# Insole_ver1_chi.net
KiCad netlist of a schematic drawn in Altium Designer
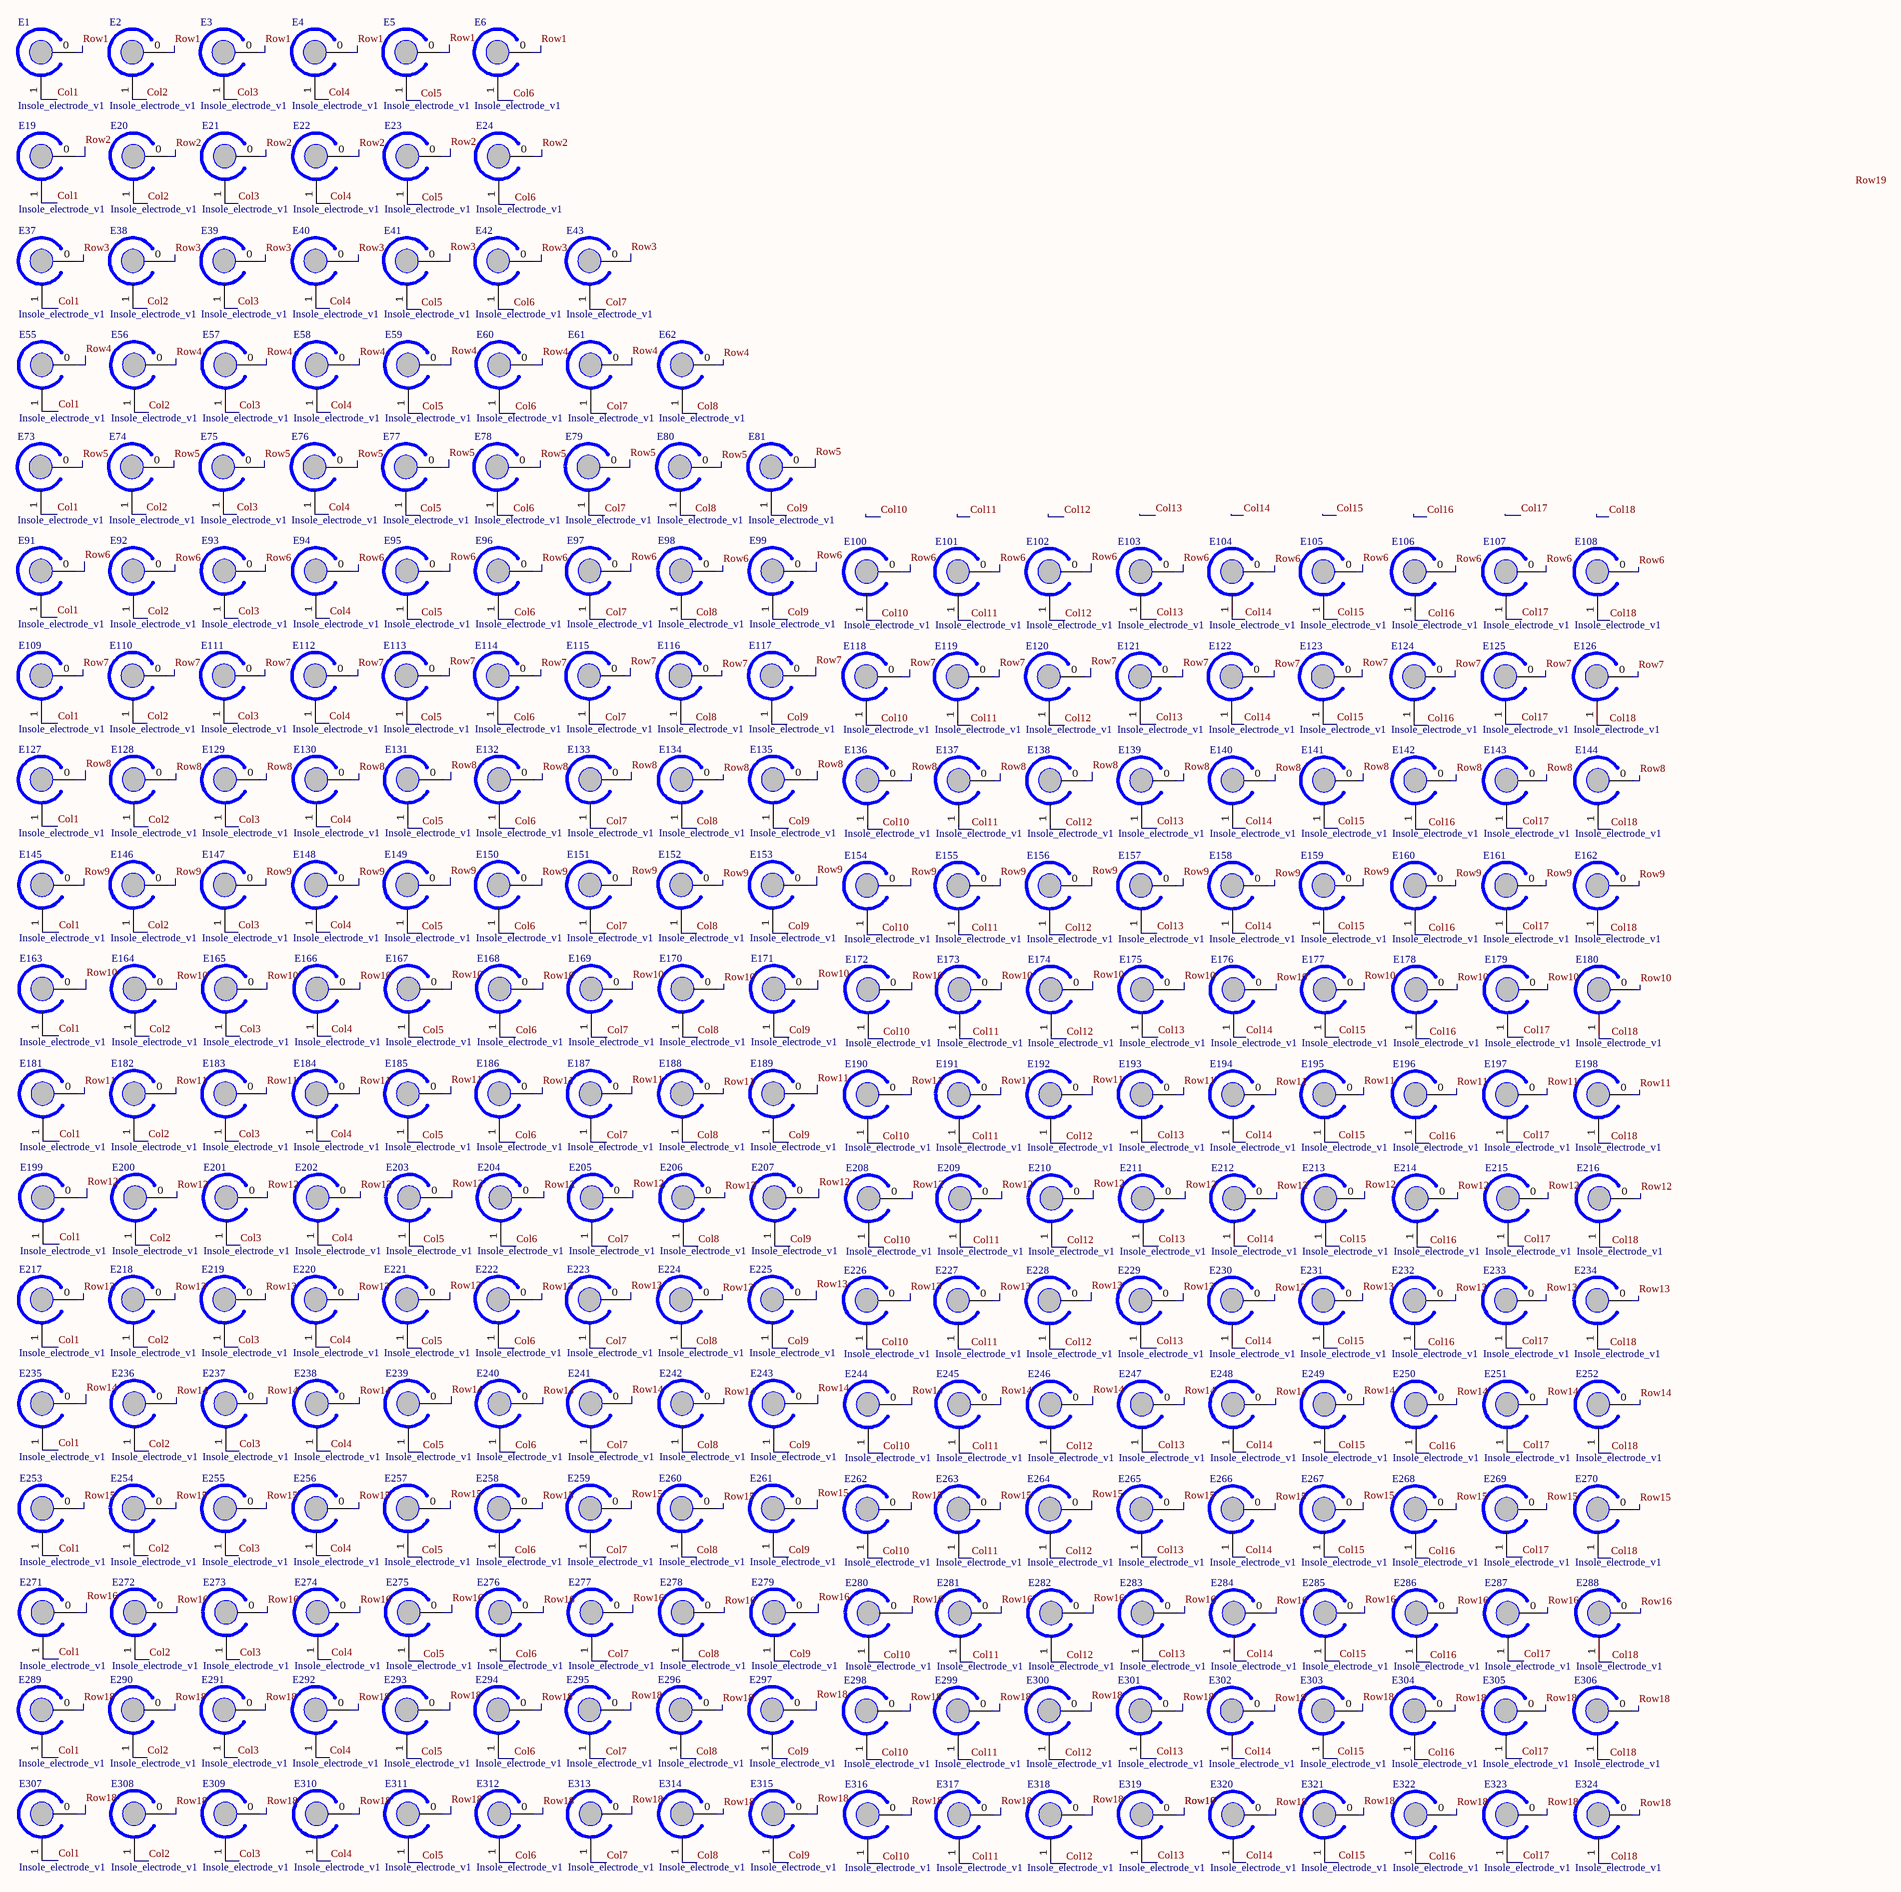
[diagram p0: Insole_ver1_chi.SchDoc]

(export (version "E")
  (design (tool "Eeschema 10.0.6"))
  (components
    (comp (ref "E1")
      (value "Insole_electrode_v1")
      (footprint "insole_electrode_v1")
      (libsource (lib "UCL") (part "Insole_electrode_v1"))
    )
    (comp (ref "E2")
      (value "Insole_electrode_v1")
      (footprint "insole_electrode_v1")
      (libsource (lib "UCL") (part "Insole_electrode_v1"))
    )
    (comp (ref "E3")
      (value "Insole_electrode_v1")
      (footprint "insole_electrode_v1")
      (libsource (lib "UCL") (part "Insole_electrode_v1"))
    )
    (comp (ref "E4")
      (value "Insole_electrode_v1")
      (footprint "insole_electrode_v1")
      (libsource (lib "UCL") (part "Insole_electrode_v1"))
    )
    (comp (ref "E5")
      (value "Insole_electrode_v1")
      (footprint "insole_electrode_v1")
      (libsource (lib "UCL") (part "Insole_electrode_v1"))
    )
    (comp (ref "E6")
      (value "Insole_electrode_v1")
      (footprint "insole_electrode_v1")
      (libsource (lib "UCL") (part "Insole_electrode_v1"))
    )
    (comp (ref "E19")
      (value "Insole_electrode_v1")
      (footprint "insole_electrode_v1")
      (libsource (lib "UCL") (part "Insole_electrode_v1"))
    )
    (comp (ref "E20")
      (value "Insole_electrode_v1")
      (footprint "insole_electrode_v1")
      (libsource (lib "UCL") (part "Insole_electrode_v1"))
    )
    (comp (ref "E21")
      (value "Insole_electrode_v1")
      (footprint "insole_electrode_v1")
      (libsource (lib "UCL") (part "Insole_electrode_v1"))
    )
    (comp (ref "E22")
      (value "Insole_electrode_v1")
      (footprint "insole_electrode_v1")
      (libsource (lib "UCL") (part "Insole_electrode_v1"))
    )
    (comp (ref "E23")
      (value "Insole_electrode_v1")
      (footprint "insole_electrode_v1")
      (libsource (lib "UCL") (part "Insole_electrode_v1"))
    )
    (comp (ref "E24")
      (value "Insole_electrode_v1")
      (footprint "insole_electrode_v1")
      (libsource (lib "UCL") (part "Insole_electrode_v1"))
    )
    (comp (ref "E37")
      (value "Insole_electrode_v1")
      (footprint "insole_electrode_v1")
      (libsource (lib "UCL") (part "Insole_electrode_v1"))
    )
    (comp (ref "E38")
      (value "Insole_electrode_v1")
      (footprint "insole_electrode_v1")
      (libsource (lib "UCL") (part "Insole_electrode_v1"))
    )
    (comp (ref "E39")
      (value "Insole_electrode_v1")
      (footprint "insole_electrode_v1")
      (libsource (lib "UCL") (part "Insole_electrode_v1"))
    )
    (comp (ref "E40")
      (value "Insole_electrode_v1")
      (footprint "insole_electrode_v1")
      (libsource (lib "UCL") (part "Insole_electrode_v1"))
    )
    (comp (ref "E41")
      (value "Insole_electrode_v1")
      (footprint "insole_electrode_v1")
      (libsource (lib "UCL") (part "Insole_electrode_v1"))
    )
    (comp (ref "E42")
      (value "Insole_electrode_v1")
      (footprint "insole_electrode_v1")
      (libsource (lib "UCL") (part "Insole_electrode_v1"))
    )
    (comp (ref "E43")
      (value "Insole_electrode_v1")
      (footprint "insole_electrode_v1")
      (libsource (lib "UCL") (part "Insole_electrode_v1"))
    )
    (comp (ref "E55")
      (value "Insole_electrode_v1")
      (footprint "insole_electrode_v1")
      (libsource (lib "UCL") (part "Insole_electrode_v1"))
    )
    (comp (ref "E56")
      (value "Insole_electrode_v1")
      (footprint "insole_electrode_v1")
      (libsource (lib "UCL") (part "Insole_electrode_v1"))
    )
    (comp (ref "E57")
      (value "Insole_electrode_v1")
      (footprint "insole_electrode_v1")
      (libsource (lib "UCL") (part "Insole_electrode_v1"))
    )
    (comp (ref "E58")
      (value "Insole_electrode_v1")
      (footprint "insole_electrode_v1")
      (libsource (lib "UCL") (part "Insole_electrode_v1"))
    )
    (comp (ref "E59")
      (value "Insole_electrode_v1")
      (footprint "insole_electrode_v1")
      (libsource (lib "UCL") (part "Insole_electrode_v1"))
    )
    (comp (ref "E60")
      (value "Insole_electrode_v1")
      (footprint "insole_electrode_v1")
      (libsource (lib "UCL") (part "Insole_electrode_v1"))
    )
    (comp (ref "E61")
      (value "Insole_electrode_v1")
      (footprint "insole_electrode_v1")
      (libsource (lib "UCL") (part "Insole_electrode_v1"))
    )
    (comp (ref "E62")
      (value "Insole_electrode_v1")
      (footprint "insole_electrode_v1")
      (libsource (lib "UCL") (part "Insole_electrode_v1"))
    )
    (comp (ref "E73")
      (value "Insole_electrode_v1")
      (footprint "insole_electrode_v1")
      (libsource (lib "UCL") (part "Insole_electrode_v1"))
    )
    (comp (ref "E74")
      (value "Insole_electrode_v1")
      (footprint "insole_electrode_v1")
      (libsource (lib "UCL") (part "Insole_electrode_v1"))
    )
    (comp (ref "E75")
      (value "Insole_electrode_v1")
      (footprint "insole_electrode_v1")
      (libsource (lib "UCL") (part "Insole_electrode_v1"))
    )
    (comp (ref "E76")
      (value "Insole_electrode_v1")
      (footprint "insole_electrode_v1")
      (libsource (lib "UCL") (part "Insole_electrode_v1"))
    )
    (comp (ref "E77")
      (value "Insole_electrode_v1")
      (footprint "insole_electrode_v1")
      (libsource (lib "UCL") (part "Insole_electrode_v1"))
    )
    (comp (ref "E78")
      (value "Insole_electrode_v1")
      (footprint "insole_electrode_v1")
      (libsource (lib "UCL") (part "Insole_electrode_v1"))
    )
    (comp (ref "E79")
      (value "Insole_electrode_v1")
      (footprint "insole_electrode_v1")
      (libsource (lib "UCL") (part "Insole_electrode_v1"))
    )
    (comp (ref "E80")
      (value "Insole_electrode_v1")
      (footprint "insole_electrode_v1")
      (libsource (lib "UCL") (part "Insole_electrode_v1"))
    )
    (comp (ref "E81")
      (value "Insole_electrode_v1")
      (footprint "insole_electrode_v1")
      (libsource (lib "UCL") (part "Insole_electrode_v1"))
    )
    (comp (ref "E91")
      (value "Insole_electrode_v1")
      (footprint "insole_electrode_v1")
      (libsource (lib "UCL") (part "Insole_electrode_v1"))
    )
    (comp (ref "E92")
      (value "Insole_electrode_v1")
      (footprint "insole_electrode_v1")
      (libsource (lib "UCL") (part "Insole_electrode_v1"))
    )
    (comp (ref "E93")
      (value "Insole_electrode_v1")
      (footprint "insole_electrode_v1")
      (libsource (lib "UCL") (part "Insole_electrode_v1"))
    )
    (comp (ref "E94")
      (value "Insole_electrode_v1")
      (footprint "insole_electrode_v1")
      (libsource (lib "UCL") (part "Insole_electrode_v1"))
    )
    (comp (ref "E95")
      (value "Insole_electrode_v1")
      (footprint "insole_electrode_v1")
      (libsource (lib "UCL") (part "Insole_electrode_v1"))
    )
    (comp (ref "E96")
      (value "Insole_electrode_v1")
      (footprint "insole_electrode_v1")
      (libsource (lib "UCL") (part "Insole_electrode_v1"))
    )
    (comp (ref "E97")
      (value "Insole_electrode_v1")
      (footprint "insole_electrode_v1")
      (libsource (lib "UCL") (part "Insole_electrode_v1"))
    )
    (comp (ref "E98")
      (value "Insole_electrode_v1")
      (footprint "insole_electrode_v1")
      (libsource (lib "UCL") (part "Insole_electrode_v1"))
    )
    (comp (ref "E99")
      (value "Insole_electrode_v1")
      (footprint "insole_electrode_v1")
      (libsource (lib "UCL") (part "Insole_electrode_v1"))
    )
    (comp (ref "E100")
      (value "Insole_electrode_v1")
      (footprint "insole_electrode_v1")
      (libsource (lib "UCL") (part "Insole_electrode_v1"))
    )
    (comp (ref "E101")
      (value "Insole_electrode_v1")
      (footprint "insole_electrode_v1")
      (libsource (lib "UCL") (part "Insole_electrode_v1"))
    )
    (comp (ref "E102")
      (value "Insole_electrode_v1")
      (footprint "insole_electrode_v1")
      (libsource (lib "UCL") (part "Insole_electrode_v1"))
    )
    (comp (ref "E103")
      (value "Insole_electrode_v1")
      (footprint "insole_electrode_v1")
      (libsource (lib "UCL") (part "Insole_electrode_v1"))
    )
    (comp (ref "E104")
      (value "Insole_electrode_v1")
      (footprint "insole_electrode_v1")
      (libsource (lib "UCL") (part "Insole_electrode_v1"))
    )
    (comp (ref "E105")
      (value "Insole_electrode_v1")
      (footprint "insole_electrode_v1")
      (libsource (lib "UCL") (part "Insole_electrode_v1"))
    )
    (comp (ref "E106")
      (value "Insole_electrode_v1")
      (footprint "insole_electrode_v1")
      (libsource (lib "UCL") (part "Insole_electrode_v1"))
    )
    (comp (ref "E107")
      (value "Insole_electrode_v1")
      (footprint "insole_electrode_v1")
      (libsource (lib "UCL") (part "Insole_electrode_v1"))
    )
    (comp (ref "E108")
      (value "Insole_electrode_v1")
      (footprint "insole_electrode_v1")
      (libsource (lib "UCL") (part "Insole_electrode_v1"))
    )
    (comp (ref "E109")
      (value "Insole_electrode_v1")
      (footprint "insole_electrode_v1")
      (libsource (lib "UCL") (part "Insole_electrode_v1"))
    )
    (comp (ref "E110")
      (value "Insole_electrode_v1")
      (footprint "insole_electrode_v1")
      (libsource (lib "UCL") (part "Insole_electrode_v1"))
    )
    (comp (ref "E111")
      (value "Insole_electrode_v1")
      (footprint "insole_electrode_v1")
      (libsource (lib "UCL") (part "Insole_electrode_v1"))
    )
    (comp (ref "E112")
      (value "Insole_electrode_v1")
      (footprint "insole_electrode_v1")
      (libsource (lib "UCL") (part "Insole_electrode_v1"))
    )
    (comp (ref "E113")
      (value "Insole_electrode_v1")
      (footprint "insole_electrode_v1")
      (libsource (lib "UCL") (part "Insole_electrode_v1"))
    )
    (comp (ref "E114")
      (value "Insole_electrode_v1")
      (footprint "insole_electrode_v1")
      (libsource (lib "UCL") (part "Insole_electrode_v1"))
    )
    (comp (ref "E115")
      (value "Insole_electrode_v1")
      (footprint "insole_electrode_v1")
      (libsource (lib "UCL") (part "Insole_electrode_v1"))
    )
    (comp (ref "E116")
      (value "Insole_electrode_v1")
      (footprint "insole_electrode_v1")
      (libsource (lib "UCL") (part "Insole_electrode_v1"))
    )
    (comp (ref "E117")
      (value "Insole_electrode_v1")
      (footprint "insole_electrode_v1")
      (libsource (lib "UCL") (part "Insole_electrode_v1"))
    )
    (comp (ref "E118")
      (value "Insole_electrode_v1")
      (footprint "insole_electrode_v1")
      (libsource (lib "UCL") (part "Insole_electrode_v1"))
    )
    (comp (ref "E119")
      (value "Insole_electrode_v1")
      (footprint "insole_electrode_v1")
      (libsource (lib "UCL") (part "Insole_electrode_v1"))
    )
    (comp (ref "E120")
      (value "Insole_electrode_v1")
      (footprint "insole_electrode_v1")
      (libsource (lib "UCL") (part "Insole_electrode_v1"))
    )
    (comp (ref "E121")
      (value "Insole_electrode_v1")
      (footprint "insole_electrode_v1")
      (libsource (lib "UCL") (part "Insole_electrode_v1"))
    )
    (comp (ref "E122")
      (value "Insole_electrode_v1")
      (footprint "insole_electrode_v1")
      (libsource (lib "UCL") (part "Insole_electrode_v1"))
    )
    (comp (ref "E123")
      (value "Insole_electrode_v1")
      (footprint "insole_electrode_v1")
      (libsource (lib "UCL") (part "Insole_electrode_v1"))
    )
    (comp (ref "E124")
      (value "Insole_electrode_v1")
      (footprint "insole_electrode_v1")
      (libsource (lib "UCL") (part "Insole_electrode_v1"))
    )
    (comp (ref "E125")
      (value "Insole_electrode_v1")
      (footprint "insole_electrode_v1")
      (libsource (lib "UCL") (part "Insole_electrode_v1"))
    )
    (comp (ref "E126")
      (value "Insole_electrode_v1")
      (footprint "insole_electrode_v1")
      (libsource (lib "UCL") (part "Insole_electrode_v1"))
    )
    (comp (ref "E127")
      (value "Insole_electrode_v1")
      (footprint "insole_electrode_v1")
      (libsource (lib "UCL") (part "Insole_electrode_v1"))
    )
    (comp (ref "E128")
      (value "Insole_electrode_v1")
      (footprint "insole_electrode_v1")
      (libsource (lib "UCL") (part "Insole_electrode_v1"))
    )
    (comp (ref "E129")
      (value "Insole_electrode_v1")
      (footprint "insole_electrode_v1")
      (libsource (lib "UCL") (part "Insole_electrode_v1"))
    )
    (comp (ref "E130")
      (value "Insole_electrode_v1")
      (footprint "insole_electrode_v1")
      (libsource (lib "UCL") (part "Insole_electrode_v1"))
    )
    (comp (ref "E131")
      (value "Insole_electrode_v1")
      (footprint "insole_electrode_v1")
      (libsource (lib "UCL") (part "Insole_electrode_v1"))
    )
    (comp (ref "E132")
      (value "Insole_electrode_v1")
      (footprint "insole_electrode_v1")
      (libsource (lib "UCL") (part "Insole_electrode_v1"))
    )
    (comp (ref "E133")
      (value "Insole_electrode_v1")
      (footprint "insole_electrode_v1")
      (libsource (lib "UCL") (part "Insole_electrode_v1"))
    )
    (comp (ref "E134")
      (value "Insole_electrode_v1")
      (footprint "insole_electrode_v1")
      (libsource (lib "UCL") (part "Insole_electrode_v1"))
    )
    (comp (ref "E135")
      (value "Insole_electrode_v1")
      (footprint "insole_electrode_v1")
      (libsource (lib "UCL") (part "Insole_electrode_v1"))
    )
    (comp (ref "E136")
      (value "Insole_electrode_v1")
      (footprint "insole_electrode_v1")
      (libsource (lib "UCL") (part "Insole_electrode_v1"))
    )
    (comp (ref "E137")
      (value "Insole_electrode_v1")
      (footprint "insole_electrode_v1")
      (libsource (lib "UCL") (part "Insole_electrode_v1"))
    )
    (comp (ref "E138")
      (value "Insole_electrode_v1")
      (footprint "insole_electrode_v1")
      (libsource (lib "UCL") (part "Insole_electrode_v1"))
    )
    (comp (ref "E139")
      (value "Insole_electrode_v1")
      (footprint "insole_electrode_v1")
      (libsource (lib "UCL") (part "Insole_electrode_v1"))
    )
    (comp (ref "E140")
      (value "Insole_electrode_v1")
      (footprint "insole_electrode_v1")
      (libsource (lib "UCL") (part "Insole_electrode_v1"))
    )
    (comp (ref "E141")
      (value "Insole_electrode_v1")
      (footprint "insole_electrode_v1")
      (libsource (lib "UCL") (part "Insole_electrode_v1"))
    )
    (comp (ref "E142")
      (value "Insole_electrode_v1")
      (footprint "insole_electrode_v1")
      (libsource (lib "UCL") (part "Insole_electrode_v1"))
    )
    (comp (ref "E143")
      (value "Insole_electrode_v1")
      (footprint "insole_electrode_v1")
      (libsource (lib "UCL") (part "Insole_electrode_v1"))
    )
    (comp (ref "E144")
      (value "Insole_electrode_v1")
      (footprint "insole_electrode_v1")
      (libsource (lib "UCL") (part "Insole_electrode_v1"))
    )
    (comp (ref "E145")
      (value "Insole_electrode_v1")
      (footprint "insole_electrode_v1")
      (libsource (lib "UCL") (part "Insole_electrode_v1"))
    )
    (comp (ref "E146")
      (value "Insole_electrode_v1")
      (footprint "insole_electrode_v1")
      (libsource (lib "UCL") (part "Insole_electrode_v1"))
    )
    (comp (ref "E147")
      (value "Insole_electrode_v1")
      (footprint "insole_electrode_v1")
      (libsource (lib "UCL") (part "Insole_electrode_v1"))
    )
    (comp (ref "E148")
      (value "Insole_electrode_v1")
      (footprint "insole_electrode_v1")
      (libsource (lib "UCL") (part "Insole_electrode_v1"))
    )
    (comp (ref "E149")
      (value "Insole_electrode_v1")
      (footprint "insole_electrode_v1")
      (libsource (lib "UCL") (part "Insole_electrode_v1"))
    )
    (comp (ref "E150")
      (value "Insole_electrode_v1")
      (footprint "insole_electrode_v1")
      (libsource (lib "UCL") (part "Insole_electrode_v1"))
    )
    (comp (ref "E151")
      (value "Insole_electrode_v1")
      (footprint "insole_electrode_v1")
      (libsource (lib "UCL") (part "Insole_electrode_v1"))
    )
    (comp (ref "E152")
      (value "Insole_electrode_v1")
      (footprint "insole_electrode_v1")
      (libsource (lib "UCL") (part "Insole_electrode_v1"))
    )
    (comp (ref "E153")
      (value "Insole_electrode_v1")
      (footprint "insole_electrode_v1")
      (libsource (lib "UCL") (part "Insole_electrode_v1"))
    )
    (comp (ref "E154")
      (value "Insole_electrode_v1")
      (footprint "insole_electrode_v1")
      (libsource (lib "UCL") (part "Insole_electrode_v1"))
    )
    (comp (ref "E155")
      (value "Insole_electrode_v1")
      (footprint "insole_electrode_v1")
      (libsource (lib "UCL") (part "Insole_electrode_v1"))
    )
    (comp (ref "E156")
      (value "Insole_electrode_v1")
      (footprint "insole_electrode_v1")
      (libsource (lib "UCL") (part "Insole_electrode_v1"))
    )
    (comp (ref "E157")
      (value "Insole_electrode_v1")
      (footprint "insole_electrode_v1")
      (libsource (lib "UCL") (part "Insole_electrode_v1"))
    )
    (comp (ref "E158")
      (value "Insole_electrode_v1")
      (footprint "insole_electrode_v1")
      (libsource (lib "UCL") (part "Insole_electrode_v1"))
    )
    (comp (ref "E159")
      (value "Insole_electrode_v1")
      (footprint "insole_electrode_v1")
      (libsource (lib "UCL") (part "Insole_electrode_v1"))
    )
    (comp (ref "E160")
      (value "Insole_electrode_v1")
      (footprint "insole_electrode_v1")
      (libsource (lib "UCL") (part "Insole_electrode_v1"))
    )
    (comp (ref "E161")
      (value "Insole_electrode_v1")
      (footprint "insole_electrode_v1")
      (libsource (lib "UCL") (part "Insole_electrode_v1"))
    )
    (comp (ref "E162")
      (value "Insole_electrode_v1")
      (footprint "insole_electrode_v1")
      (libsource (lib "UCL") (part "Insole_electrode_v1"))
    )
    (comp (ref "E163")
      (value "Insole_electrode_v1")
      (footprint "insole_electrode_v1")
      (libsource (lib "UCL") (part "Insole_electrode_v1"))
    )
    (comp (ref "E164")
      (value "Insole_electrode_v1")
      (footprint "insole_electrode_v1")
      (libsource (lib "UCL") (part "Insole_electrode_v1"))
    )
    (comp (ref "E165")
      (value "Insole_electrode_v1")
      (footprint "insole_electrode_v1")
      (libsource (lib "UCL") (part "Insole_electrode_v1"))
    )
    (comp (ref "E166")
      (value "Insole_electrode_v1")
      (footprint "insole_electrode_v1")
      (libsource (lib "UCL") (part "Insole_electrode_v1"))
    )
    (comp (ref "E167")
      (value "Insole_electrode_v1")
      (footprint "insole_electrode_v1")
      (libsource (lib "UCL") (part "Insole_electrode_v1"))
    )
    (comp (ref "E168")
      (value "Insole_electrode_v1")
      (footprint "insole_electrode_v1")
      (libsource (lib "UCL") (part "Insole_electrode_v1"))
    )
    (comp (ref "E169")
      (value "Insole_electrode_v1")
      (footprint "insole_electrode_v1")
      (libsource (lib "UCL") (part "Insole_electrode_v1"))
    )
    (comp (ref "E170")
      (value "Insole_electrode_v1")
      (footprint "insole_electrode_v1")
      (libsource (lib "UCL") (part "Insole_electrode_v1"))
    )
    (comp (ref "E171")
      (value "Insole_electrode_v1")
      (footprint "insole_electrode_v1")
      (libsource (lib "UCL") (part "Insole_electrode_v1"))
    )
    (comp (ref "E172")
      (value "Insole_electrode_v1")
      (footprint "insole_electrode_v1")
      (libsource (lib "UCL") (part "Insole_electrode_v1"))
    )
    (comp (ref "E173")
      (value "Insole_electrode_v1")
      (footprint "insole_electrode_v1")
      (libsource (lib "UCL") (part "Insole_electrode_v1"))
    )
    (comp (ref "E174")
      (value "Insole_electrode_v1")
      (footprint "insole_electrode_v1")
      (libsource (lib "UCL") (part "Insole_electrode_v1"))
    )
    (comp (ref "E175")
      (value "Insole_electrode_v1")
      (footprint "insole_electrode_v1")
      (libsource (lib "UCL") (part "Insole_electrode_v1"))
    )
    (comp (ref "E176")
      (value "Insole_electrode_v1")
      (footprint "insole_electrode_v1")
      (libsource (lib "UCL") (part "Insole_electrode_v1"))
    )
    (comp (ref "E177")
      (value "Insole_electrode_v1")
      (footprint "insole_electrode_v1")
      (libsource (lib "UCL") (part "Insole_electrode_v1"))
    )
    (comp (ref "E178")
      (value "Insole_electrode_v1")
      (footprint "insole_electrode_v1")
      (libsource (lib "UCL") (part "Insole_electrode_v1"))
    )
    (comp (ref "E179")
      (value "Insole_electrode_v1")
      (footprint "insole_electrode_v1")
      (libsource (lib "UCL") (part "Insole_electrode_v1"))
    )
    (comp (ref "E180")
      (value "Insole_electrode_v1")
      (footprint "insole_electrode_v1")
      (libsource (lib "UCL") (part "Insole_electrode_v1"))
    )
    (comp (ref "E181")
      (value "Insole_electrode_v1")
      (footprint "insole_electrode_v1")
      (libsource (lib "UCL") (part "Insole_electrode_v1"))
    )
    (comp (ref "E182")
      (value "Insole_electrode_v1")
      (footprint "insole_electrode_v1")
      (libsource (lib "UCL") (part "Insole_electrode_v1"))
    )
    (comp (ref "E183")
      (value "Insole_electrode_v1")
      (footprint "insole_electrode_v1")
      (libsource (lib "UCL") (part "Insole_electrode_v1"))
    )
    (comp (ref "E184")
      (value "Insole_electrode_v1")
      (footprint "insole_electrode_v1")
      (libsource (lib "UCL") (part "Insole_electrode_v1"))
    )
    (comp (ref "E185")
      (value "Insole_electrode_v1")
      (footprint "insole_electrode_v1")
      (libsource (lib "UCL") (part "Insole_electrode_v1"))
    )
    (comp (ref "E186")
      (value "Insole_electrode_v1")
      (footprint "insole_electrode_v1")
      (libsource (lib "UCL") (part "Insole_electrode_v1"))
    )
    (comp (ref "E187")
      (value "Insole_electrode_v1")
      (footprint "insole_electrode_v1")
      (libsource (lib "UCL") (part "Insole_electrode_v1"))
    )
    (comp (ref "E188")
      (value "Insole_electrode_v1")
      (footprint "insole_electrode_v1")
      (libsource (lib "UCL") (part "Insole_electrode_v1"))
    )
    (comp (ref "E189")
      (value "Insole_electrode_v1")
      (footprint "insole_electrode_v1")
      (libsource (lib "UCL") (part "Insole_electrode_v1"))
    )
    (comp (ref "E190")
      (value "Insole_electrode_v1")
      (footprint "insole_electrode_v1")
      (libsource (lib "UCL") (part "Insole_electrode_v1"))
    )
    (comp (ref "E191")
      (value "Insole_electrode_v1")
      (footprint "insole_electrode_v1")
      (libsource (lib "UCL") (part "Insole_electrode_v1"))
    )
    (comp (ref "E192")
      (value "Insole_electrode_v1")
      (footprint "insole_electrode_v1")
      (libsource (lib "UCL") (part "Insole_electrode_v1"))
    )
    (comp (ref "E193")
      (value "Insole_electrode_v1")
      (footprint "insole_electrode_v1")
      (libsource (lib "UCL") (part "Insole_electrode_v1"))
    )
    (comp (ref "E194")
      (value "Insole_electrode_v1")
      (footprint "insole_electrode_v1")
      (libsource (lib "UCL") (part "Insole_electrode_v1"))
    )
    (comp (ref "E195")
      (value "Insole_electrode_v1")
      (footprint "insole_electrode_v1")
      (libsource (lib "UCL") (part "Insole_electrode_v1"))
    )
    (comp (ref "E196")
      (value "Insole_electrode_v1")
      (footprint "insole_electrode_v1")
      (libsource (lib "UCL") (part "Insole_electrode_v1"))
    )
    (comp (ref "E197")
      (value "Insole_electrode_v1")
      (footprint "insole_electrode_v1")
      (libsource (lib "UCL") (part "Insole_electrode_v1"))
    )
    (comp (ref "E198")
      (value "Insole_electrode_v1")
      (footprint "insole_electrode_v1")
      (libsource (lib "UCL") (part "Insole_electrode_v1"))
    )
    (comp (ref "E199")
      (value "Insole_electrode_v1")
      (footprint "insole_electrode_v1")
      (libsource (lib "UCL") (part "Insole_electrode_v1"))
    )
    (comp (ref "E200")
      (value "Insole_electrode_v1")
      (footprint "insole_electrode_v1")
      (libsource (lib "UCL") (part "Insole_electrode_v1"))
    )
    (comp (ref "E201")
      (value "Insole_electrode_v1")
      (footprint "insole_electrode_v1")
      (libsource (lib "UCL") (part "Insole_electrode_v1"))
    )
    (comp (ref "E202")
      (value "Insole_electrode_v1")
      (footprint "insole_electrode_v1")
      (libsource (lib "UCL") (part "Insole_electrode_v1"))
    )
    (comp (ref "E203")
      (value "Insole_electrode_v1")
      (footprint "insole_electrode_v1")
      (libsource (lib "UCL") (part "Insole_electrode_v1"))
    )
    (comp (ref "E204")
      (value "Insole_electrode_v1")
      (footprint "insole_electrode_v1")
      (libsource (lib "UCL") (part "Insole_electrode_v1"))
    )
    (comp (ref "E205")
      (value "Insole_electrode_v1")
      (footprint "insole_electrode_v1")
      (libsource (lib "UCL") (part "Insole_electrode_v1"))
    )
    (comp (ref "E206")
      (value "Insole_electrode_v1")
      (footprint "insole_electrode_v1")
      (libsource (lib "UCL") (part "Insole_electrode_v1"))
    )
    (comp (ref "E207")
      (value "Insole_electrode_v1")
      (footprint "insole_electrode_v1")
      (libsource (lib "UCL") (part "Insole_electrode_v1"))
    )
    (comp (ref "E208")
      (value "Insole_electrode_v1")
      (footprint "insole_electrode_v1")
      (libsource (lib "UCL") (part "Insole_electrode_v1"))
    )
    (comp (ref "E209")
      (value "Insole_electrode_v1")
      (footprint "insole_electrode_v1")
      (libsource (lib "UCL") (part "Insole_electrode_v1"))
    )
    (comp (ref "E210")
      (value "Insole_electrode_v1")
      (footprint "insole_electrode_v1")
      (libsource (lib "UCL") (part "Insole_electrode_v1"))
    )
    (comp (ref "E211")
      (value "Insole_electrode_v1")
      (footprint "insole_electrode_v1")
      (libsource (lib "UCL") (part "Insole_electrode_v1"))
    )
    (comp (ref "E212")
      (value "Insole_electrode_v1")
      (footprint "insole_electrode_v1")
      (libsource (lib "UCL") (part "Insole_electrode_v1"))
    )
    (comp (ref "E213")
      (value "Insole_electrode_v1")
      (footprint "insole_electrode_v1")
      (libsource (lib "UCL") (part "Insole_electrode_v1"))
    )
    (comp (ref "E214")
      (value "Insole_electrode_v1")
      (footprint "insole_electrode_v1")
      (libsource (lib "UCL") (part "Insole_electrode_v1"))
    )
    (comp (ref "E215")
      (value "Insole_electrode_v1")
      (footprint "insole_electrode_v1")
      (libsource (lib "UCL") (part "Insole_electrode_v1"))
    )
    (comp (ref "E216")
      (value "Insole_electrode_v1")
      (footprint "insole_electrode_v1")
      (libsource (lib "UCL") (part "Insole_electrode_v1"))
    )
    (comp (ref "E217")
      (value "Insole_electrode_v1")
      (footprint "insole_electrode_v1")
      (libsource (lib "UCL") (part "Insole_electrode_v1"))
    )
    (comp (ref "E218")
      (value "Insole_electrode_v1")
      (footprint "insole_electrode_v1")
      (libsource (lib "UCL") (part "Insole_electrode_v1"))
    )
    (comp (ref "E219")
      (value "Insole_electrode_v1")
      (footprint "insole_electrode_v1")
      (libsource (lib "UCL") (part "Insole_electrode_v1"))
    )
    (comp (ref "E220")
      (value "Insole_electrode_v1")
      (footprint "insole_electrode_v1")
      (libsource (lib "UCL") (part "Insole_electrode_v1"))
    )
    (comp (ref "E221")
      (value "Insole_electrode_v1")
      (footprint "insole_electrode_v1")
      (libsource (lib "UCL") (part "Insole_electrode_v1"))
    )
    (comp (ref "E222")
      (value "Insole_electrode_v1")
      (footprint "insole_electrode_v1")
      (libsource (lib "UCL") (part "Insole_electrode_v1"))
    )
    (comp (ref "E223")
      (value "Insole_electrode_v1")
      (footprint "insole_electrode_v1")
      (libsource (lib "UCL") (part "Insole_electrode_v1"))
    )
    (comp (ref "E224")
      (value "Insole_electrode_v1")
      (footprint "insole_electrode_v1")
      (libsource (lib "UCL") (part "Insole_electrode_v1"))
    )
    (comp (ref "E225")
      (value "Insole_electrode_v1")
      (footprint "insole_electrode_v1")
      (libsource (lib "UCL") (part "Insole_electrode_v1"))
    )
    (comp (ref "E226")
      (value "Insole_electrode_v1")
      (footprint "insole_electrode_v1")
      (libsource (lib "UCL") (part "Insole_electrode_v1"))
    )
    (comp (ref "E227")
      (value "Insole_electrode_v1")
      (footprint "insole_electrode_v1")
      (libsource (lib "UCL") (part "Insole_electrode_v1"))
    )
    (comp (ref "E228")
      (value "Insole_electrode_v1")
      (footprint "insole_electrode_v1")
      (libsource (lib "UCL") (part "Insole_electrode_v1"))
    )
    (comp (ref "E229")
      (value "Insole_electrode_v1")
      (footprint "insole_electrode_v1")
      (libsource (lib "UCL") (part "Insole_electrode_v1"))
    )
    (comp (ref "E230")
      (value "Insole_electrode_v1")
      (footprint "insole_electrode_v1")
      (libsource (lib "UCL") (part "Insole_electrode_v1"))
    )
    (comp (ref "E231")
      (value "Insole_electrode_v1")
      (footprint "insole_electrode_v1")
      (libsource (lib "UCL") (part "Insole_electrode_v1"))
    )
    (comp (ref "E232")
      (value "Insole_electrode_v1")
      (footprint "insole_electrode_v1")
      (libsource (lib "UCL") (part "Insole_electrode_v1"))
    )
    (comp (ref "E233")
      (value "Insole_electrode_v1")
      (footprint "insole_electrode_v1")
      (libsource (lib "UCL") (part "Insole_electrode_v1"))
    )
    (comp (ref "E234")
      (value "Insole_electrode_v1")
      (footprint "insole_electrode_v1")
      (libsource (lib "UCL") (part "Insole_electrode_v1"))
    )
    (comp (ref "E235")
      (value "Insole_electrode_v1")
      (footprint "insole_electrode_v1")
      (libsource (lib "UCL") (part "Insole_electrode_v1"))
    )
    (comp (ref "E236")
      (value "Insole_electrode_v1")
      (footprint "insole_electrode_v1")
      (libsource (lib "UCL") (part "Insole_electrode_v1"))
    )
    (comp (ref "E237")
      (value "Insole_electrode_v1")
      (footprint "insole_electrode_v1")
      (libsource (lib "UCL") (part "Insole_electrode_v1"))
    )
    (comp (ref "E238")
      (value "Insole_electrode_v1")
      (footprint "insole_electrode_v1")
      (libsource (lib "UCL") (part "Insole_electrode_v1"))
    )
    (comp (ref "E239")
      (value "Insole_electrode_v1")
      (footprint "insole_electrode_v1")
      (libsource (lib "UCL") (part "Insole_electrode_v1"))
    )
    (comp (ref "E240")
      (value "Insole_electrode_v1")
      (footprint "insole_electrode_v1")
      (libsource (lib "UCL") (part "Insole_electrode_v1"))
    )
    (comp (ref "E241")
      (value "Insole_electrode_v1")
      (footprint "insole_electrode_v1")
      (libsource (lib "UCL") (part "Insole_electrode_v1"))
    )
    (comp (ref "E242")
      (value "Insole_electrode_v1")
      (footprint "insole_electrode_v1")
      (libsource (lib "UCL") (part "Insole_electrode_v1"))
    )
    (comp (ref "E243")
      (value "Insole_electrode_v1")
      (footprint "insole_electrode_v1")
      (libsource (lib "UCL") (part "Insole_electrode_v1"))
    )
    (comp (ref "E244")
      (value "Insole_electrode_v1")
      (footprint "insole_electrode_v1")
      (libsource (lib "UCL") (part "Insole_electrode_v1"))
    )
    (comp (ref "E245")
      (value "Insole_electrode_v1")
      (footprint "insole_electrode_v1")
      (libsource (lib "UCL") (part "Insole_electrode_v1"))
    )
    (comp (ref "E246")
      (value "Insole_electrode_v1")
      (footprint "insole_electrode_v1")
      (libsource (lib "UCL") (part "Insole_electrode_v1"))
    )
    (comp (ref "E247")
      (value "Insole_electrode_v1")
      (footprint "insole_electrode_v1")
      (libsource (lib "UCL") (part "Insole_electrode_v1"))
    )
    (comp (ref "E248")
      (value "Insole_electrode_v1")
      (footprint "insole_electrode_v1")
      (libsource (lib "UCL") (part "Insole_electrode_v1"))
    )
    (comp (ref "E249")
      (value "Insole_electrode_v1")
      (footprint "insole_electrode_v1")
      (libsource (lib "UCL") (part "Insole_electrode_v1"))
    )
    (comp (ref "E250")
      (value "Insole_electrode_v1")
      (footprint "insole_electrode_v1")
      (libsource (lib "UCL") (part "Insole_electrode_v1"))
    )
    (comp (ref "E251")
      (value "Insole_electrode_v1")
      (footprint "insole_electrode_v1")
      (libsource (lib "UCL") (part "Insole_electrode_v1"))
    )
    (comp (ref "E252")
      (value "Insole_electrode_v1")
      (footprint "insole_electrode_v1")
      (libsource (lib "UCL") (part "Insole_electrode_v1"))
    )
    (comp (ref "E253")
      (value "Insole_electrode_v1")
      (footprint "insole_electrode_v1")
      (libsource (lib "UCL") (part "Insole_electrode_v1"))
    )
    (comp (ref "E254")
      (value "Insole_electrode_v1")
      (footprint "insole_electrode_v1")
      (libsource (lib "UCL") (part "Insole_electrode_v1"))
    )
    (comp (ref "E255")
      (value "Insole_electrode_v1")
      (footprint "insole_electrode_v1")
      (libsource (lib "UCL") (part "Insole_electrode_v1"))
    )
    (comp (ref "E256")
      (value "Insole_electrode_v1")
      (footprint "insole_electrode_v1")
      (libsource (lib "UCL") (part "Insole_electrode_v1"))
    )
    (comp (ref "E257")
      (value "Insole_electrode_v1")
      (footprint "insole_electrode_v1")
      (libsource (lib "UCL") (part "Insole_electrode_v1"))
    )
    (comp (ref "E258")
      (value "Insole_electrode_v1")
      (footprint "insole_electrode_v1")
      (libsource (lib "UCL") (part "Insole_electrode_v1"))
    )
    (comp (ref "E259")
      (value "Insole_electrode_v1")
      (footprint "insole_electrode_v1")
      (libsource (lib "UCL") (part "Insole_electrode_v1"))
    )
    (comp (ref "E260")
      (value "Insole_electrode_v1")
      (footprint "insole_electrode_v1")
      (libsource (lib "UCL") (part "Insole_electrode_v1"))
    )
    (comp (ref "E261")
      (value "Insole_electrode_v1")
      (footprint "insole_electrode_v1")
      (libsource (lib "UCL") (part "Insole_electrode_v1"))
    )
    (comp (ref "E262")
      (value "Insole_electrode_v1")
      (footprint "insole_electrode_v1")
      (libsource (lib "UCL") (part "Insole_electrode_v1"))
    )
    (comp (ref "E263")
      (value "Insole_electrode_v1")
      (footprint "insole_electrode_v1")
      (libsource (lib "UCL") (part "Insole_electrode_v1"))
    )
    (comp (ref "E264")
      (value "Insole_electrode_v1")
      (footprint "insole_electrode_v1")
      (libsource (lib "UCL") (part "Insole_electrode_v1"))
    )
    (comp (ref "E265")
      (value "Insole_electrode_v1")
      (footprint "insole_electrode_v1")
      (libsource (lib "UCL") (part "Insole_electrode_v1"))
    )
    (comp (ref "E266")
      (value "Insole_electrode_v1")
      (footprint "insole_electrode_v1")
      (libsource (lib "UCL") (part "Insole_electrode_v1"))
    )
    (comp (ref "E267")
      (value "Insole_electrode_v1")
      (footprint "insole_electrode_v1")
      (libsource (lib "UCL") (part "Insole_electrode_v1"))
    )
    (comp (ref "E268")
      (value "Insole_electrode_v1")
      (footprint "insole_electrode_v1")
      (libsource (lib "UCL") (part "Insole_electrode_v1"))
    )
    (comp (ref "E269")
      (value "Insole_electrode_v1")
      (footprint "insole_electrode_v1")
      (libsource (lib "UCL") (part "Insole_electrode_v1"))
    )
    (comp (ref "E270")
      (value "Insole_electrode_v1")
      (footprint "insole_electrode_v1")
      (libsource (lib "UCL") (part "Insole_electrode_v1"))
    )
    (comp (ref "E271")
      (value "Insole_electrode_v1")
      (footprint "insole_electrode_v1")
      (libsource (lib "UCL") (part "Insole_electrode_v1"))
    )
    (comp (ref "E272")
      (value "Insole_electrode_v1")
      (footprint "insole_electrode_v1")
      (libsource (lib "UCL") (part "Insole_electrode_v1"))
    )
    (comp (ref "E273")
      (value "Insole_electrode_v1")
      (footprint "insole_electrode_v1")
      (libsource (lib "UCL") (part "Insole_electrode_v1"))
    )
    (comp (ref "E274")
      (value "Insole_electrode_v1")
      (footprint "insole_electrode_v1")
      (libsource (lib "UCL") (part "Insole_electrode_v1"))
    )
    (comp (ref "E275")
      (value "Insole_electrode_v1")
      (footprint "insole_electrode_v1")
      (libsource (lib "UCL") (part "Insole_electrode_v1"))
    )
    (comp (ref "E276")
      (value "Insole_electrode_v1")
      (footprint "insole_electrode_v1")
      (libsource (lib "UCL") (part "Insole_electrode_v1"))
    )
    (comp (ref "E277")
      (value "Insole_electrode_v1")
      (footprint "insole_electrode_v1")
      (libsource (lib "UCL") (part "Insole_electrode_v1"))
    )
    (comp (ref "E278")
      (value "Insole_electrode_v1")
      (footprint "insole_electrode_v1")
      (libsource (lib "UCL") (part "Insole_electrode_v1"))
    )
    (comp (ref "E279")
      (value "Insole_electrode_v1")
      (footprint "insole_electrode_v1")
      (libsource (lib "UCL") (part "Insole_electrode_v1"))
    )
    (comp (ref "E280")
      (value "Insole_electrode_v1")
      (footprint "insole_electrode_v1")
      (libsource (lib "UCL") (part "Insole_electrode_v1"))
    )
    (comp (ref "E281")
      (value "Insole_electrode_v1")
      (footprint "insole_electrode_v1")
      (libsource (lib "UCL") (part "Insole_electrode_v1"))
    )
    (comp (ref "E282")
      (value "Insole_electrode_v1")
      (footprint "insole_electrode_v1")
      (libsource (lib "UCL") (part "Insole_electrode_v1"))
    )
    (comp (ref "E283")
      (value "Insole_electrode_v1")
      (footprint "insole_electrode_v1")
      (libsource (lib "UCL") (part "Insole_electrode_v1"))
    )
    (comp (ref "E284")
      (value "Insole_electrode_v1")
      (footprint "insole_electrode_v1")
      (libsource (lib "UCL") (part "Insole_electrode_v1"))
    )
    (comp (ref "E285")
      (value "Insole_electrode_v1")
      (footprint "insole_electrode_v1")
      (libsource (lib "UCL") (part "Insole_electrode_v1"))
    )
    (comp (ref "E286")
      (value "Insole_electrode_v1")
      (footprint "insole_electrode_v1")
      (libsource (lib "UCL") (part "Insole_electrode_v1"))
    )
    (comp (ref "E287")
      (value "Insole_electrode_v1")
      (footprint "insole_electrode_v1")
      (libsource (lib "UCL") (part "Insole_electrode_v1"))
    )
    (comp (ref "E288")
      (value "Insole_electrode_v1")
      (footprint "insole_electrode_v1")
      (libsource (lib "UCL") (part "Insole_electrode_v1"))
    )
    (comp (ref "E289")
      (value "Insole_electrode_v1")
      (footprint "insole_electrode_v1")
      (libsource (lib "UCL") (part "Insole_electrode_v1"))
    )
    (comp (ref "E290")
      (value "Insole_electrode_v1")
      (footprint "insole_electrode_v1")
      (libsource (lib "UCL") (part "Insole_electrode_v1"))
    )
    (comp (ref "E291")
      (value "Insole_electrode_v1")
      (footprint "insole_electrode_v1")
      (libsource (lib "UCL") (part "Insole_electrode_v1"))
    )
    (comp (ref "E292")
      (value "Insole_electrode_v1")
      (footprint "insole_electrode_v1")
      (libsource (lib "UCL") (part "Insole_electrode_v1"))
    )
    (comp (ref "E293")
      (value "Insole_electrode_v1")
      (footprint "insole_electrode_v1")
      (libsource (lib "UCL") (part "Insole_electrode_v1"))
    )
    (comp (ref "E294")
      (value "Insole_electrode_v1")
      (footprint "insole_electrode_v1")
      (libsource (lib "UCL") (part "Insole_electrode_v1"))
    )
    (comp (ref "E295")
      (value "Insole_electrode_v1")
      (footprint "insole_electrode_v1")
      (libsource (lib "UCL") (part "Insole_electrode_v1"))
    )
    (comp (ref "E296")
      (value "Insole_electrode_v1")
      (footprint "insole_electrode_v1")
      (libsource (lib "UCL") (part "Insole_electrode_v1"))
    )
    (comp (ref "E297")
      (value "Insole_electrode_v1")
      (footprint "insole_electrode_v1")
      (libsource (lib "UCL") (part "Insole_electrode_v1"))
    )
    (comp (ref "E298")
      (value "Insole_electrode_v1")
      (footprint "insole_electrode_v1")
      (libsource (lib "UCL") (part "Insole_electrode_v1"))
    )
    (comp (ref "E299")
      (value "Insole_electrode_v1")
      (footprint "insole_electrode_v1")
      (libsource (lib "UCL") (part "Insole_electrode_v1"))
    )
    (comp (ref "E300")
      (value "Insole_electrode_v1")
      (footprint "insole_electrode_v1")
      (libsource (lib "UCL") (part "Insole_electrode_v1"))
    )
    (comp (ref "E301")
      (value "Insole_electrode_v1")
      (footprint "insole_electrode_v1")
      (libsource (lib "UCL") (part "Insole_electrode_v1"))
    )
    (comp (ref "E302")
      (value "Insole_electrode_v1")
      (footprint "insole_electrode_v1")
      (libsource (lib "UCL") (part "Insole_electrode_v1"))
    )
    (comp (ref "E303")
      (value "Insole_electrode_v1")
      (footprint "insole_electrode_v1")
      (libsource (lib "UCL") (part "Insole_electrode_v1"))
    )
    (comp (ref "E304")
      (value "Insole_electrode_v1")
      (footprint "insole_electrode_v1")
      (libsource (lib "UCL") (part "Insole_electrode_v1"))
    )
    (comp (ref "E305")
      (value "Insole_electrode_v1")
      (footprint "insole_electrode_v1")
      (libsource (lib "UCL") (part "Insole_electrode_v1"))
    )
    (comp (ref "E306")
      (value "Insole_electrode_v1")
      (footprint "insole_electrode_v1")
      (libsource (lib "UCL") (part "Insole_electrode_v1"))
    )
    (comp (ref "E307")
      (value "Insole_electrode_v1")
      (footprint "insole_electrode_v1")
      (libsource (lib "UCL") (part "Insole_electrode_v1"))
    )
    (comp (ref "E308")
      (value "Insole_electrode_v1")
      (footprint "insole_electrode_v1")
      (libsource (lib "UCL") (part "Insole_electrode_v1"))
    )
    (comp (ref "E309")
      (value "Insole_electrode_v1")
      (footprint "insole_electrode_v1")
      (libsource (lib "UCL") (part "Insole_electrode_v1"))
    )
    (comp (ref "E310")
      (value "Insole_electrode_v1")
      (footprint "insole_electrode_v1")
      (libsource (lib "UCL") (part "Insole_electrode_v1"))
    )
    (comp (ref "E311")
      (value "Insole_electrode_v1")
      (footprint "insole_electrode_v1")
      (libsource (lib "UCL") (part "Insole_electrode_v1"))
    )
    (comp (ref "E312")
      (value "Insole_electrode_v1")
      (footprint "insole_electrode_v1")
      (libsource (lib "UCL") (part "Insole_electrode_v1"))
    )
    (comp (ref "E313")
      (value "Insole_electrode_v1")
      (footprint "insole_electrode_v1")
      (libsource (lib "UCL") (part "Insole_electrode_v1"))
    )
    (comp (ref "E314")
      (value "Insole_electrode_v1")
      (footprint "insole_electrode_v1")
      (libsource (lib "UCL") (part "Insole_electrode_v1"))
    )
    (comp (ref "E315")
      (value "Insole_electrode_v1")
      (footprint "insole_electrode_v1")
      (libsource (lib "UCL") (part "Insole_electrode_v1"))
    )
    (comp (ref "E316")
      (value "Insole_electrode_v1")
      (footprint "insole_electrode_v1")
      (libsource (lib "UCL") (part "Insole_electrode_v1"))
    )
    (comp (ref "E317")
      (value "Insole_electrode_v1")
      (footprint "insole_electrode_v1")
      (libsource (lib "UCL") (part "Insole_electrode_v1"))
    )
    (comp (ref "E318")
      (value "Insole_electrode_v1")
      (footprint "insole_electrode_v1")
      (libsource (lib "UCL") (part "Insole_electrode_v1"))
    )
    (comp (ref "E319")
      (value "Insole_electrode_v1")
      (footprint "insole_electrode_v1")
      (libsource (lib "UCL") (part "Insole_electrode_v1"))
    )
    (comp (ref "E320")
      (value "Insole_electrode_v1")
      (footprint "insole_electrode_v1")
      (libsource (lib "UCL") (part "Insole_electrode_v1"))
    )
    (comp (ref "E321")
      (value "Insole_electrode_v1")
      (footprint "insole_electrode_v1")
      (libsource (lib "UCL") (part "Insole_electrode_v1"))
    )
    (comp (ref "E322")
      (value "Insole_electrode_v1")
      (footprint "insole_electrode_v1")
      (libsource (lib "UCL") (part "Insole_electrode_v1"))
    )
    (comp (ref "E323")
      (value "Insole_electrode_v1")
      (footprint "insole_electrode_v1")
      (libsource (lib "UCL") (part "Insole_electrode_v1"))
    )
    (comp (ref "E324")
      (value "Insole_electrode_v1")
      (footprint "insole_electrode_v1")
      (libsource (lib "UCL") (part "Insole_electrode_v1"))
    )
  )
  (nets
    (net (code "1") (name "/Col1") (class "Default")
      (node (ref "E1") (pin "1") (pinfunction "1_1") (pintype "passive"))
      (node (ref "E109") (pin "1") (pinfunction "1_1") (pintype "passive"))
      (node (ref "E127") (pin "1") (pinfunction "1_1") (pintype "passive"))
      (node (ref "E145") (pin "1") (pinfunction "1_1") (pintype "passive"))
      (node (ref "E163") (pin "1") (pinfunction "1_1") (pintype "passive"))
      (node (ref "E181") (pin "1") (pinfunction "1_1") (pintype "passive"))
      (node (ref "E19") (pin "1") (pinfunction "1_1") (pintype "passive"))
      (node (ref "E199") (pin "1") (pinfunction "1_1") (pintype "passive"))
      (node (ref "E217") (pin "1") (pinfunction "1_1") (pintype "passive"))
      (node (ref "E235") (pin "1") (pinfunction "1_1") (pintype "passive"))
      (node (ref "E253") (pin "1") (pinfunction "1_1") (pintype "passive"))
      (node (ref "E271") (pin "1") (pinfunction "1_1") (pintype "passive"))
      (node (ref "E289") (pin "1") (pinfunction "1_1") (pintype "passive"))
      (node (ref "E307") (pin "1") (pinfunction "1_1") (pintype "passive"))
      (node (ref "E37") (pin "1") (pinfunction "1_1") (pintype "passive"))
      (node (ref "E55") (pin "1") (pinfunction "1_1") (pintype "passive"))
      (node (ref "E73") (pin "1") (pinfunction "1_1") (pintype "passive"))
      (node (ref "E91") (pin "1") (pinfunction "1_1") (pintype "passive"))
    )
    (net (code "2") (name "/Col2") (class "Default")
      (node (ref "E110") (pin "1") (pinfunction "1_1") (pintype "passive"))
      (node (ref "E128") (pin "1") (pinfunction "1_1") (pintype "passive"))
      (node (ref "E146") (pin "1") (pinfunction "1_1") (pintype "passive"))
      (node (ref "E164") (pin "1") (pinfunction "1_1") (pintype "passive"))
      (node (ref "E182") (pin "1") (pinfunction "1_1") (pintype "passive"))
      (node (ref "E2") (pin "1") (pinfunction "1_1") (pintype "passive"))
      (node (ref "E20") (pin "1") (pinfunction "1_1") (pintype "passive"))
      (node (ref "E200") (pin "1") (pinfunction "1_1") (pintype "passive"))
      (node (ref "E218") (pin "1") (pinfunction "1_1") (pintype "passive"))
      (node (ref "E236") (pin "1") (pinfunction "1_1") (pintype "passive"))
      (node (ref "E254") (pin "1") (pinfunction "1_1") (pintype "passive"))
      (node (ref "E272") (pin "1") (pinfunction "1_1") (pintype "passive"))
      (node (ref "E290") (pin "1") (pinfunction "1_1") (pintype "passive"))
      (node (ref "E308") (pin "1") (pinfunction "1_1") (pintype "passive"))
      (node (ref "E38") (pin "1") (pinfunction "1_1") (pintype "passive"))
      (node (ref "E56") (pin "1") (pinfunction "1_1") (pintype "passive"))
      (node (ref "E74") (pin "1") (pinfunction "1_1") (pintype "passive"))
      (node (ref "E92") (pin "1") (pinfunction "1_1") (pintype "passive"))
    )
    (net (code "3") (name "/Col3") (class "Default")
      (node (ref "E111") (pin "1") (pinfunction "1_1") (pintype "passive"))
      (node (ref "E129") (pin "1") (pinfunction "1_1") (pintype "passive"))
      (node (ref "E147") (pin "1") (pinfunction "1_1") (pintype "passive"))
      (node (ref "E165") (pin "1") (pinfunction "1_1") (pintype "passive"))
      (node (ref "E183") (pin "1") (pinfunction "1_1") (pintype "passive"))
      (node (ref "E201") (pin "1") (pinfunction "1_1") (pintype "passive"))
      (node (ref "E21") (pin "1") (pinfunction "1_1") (pintype "passive"))
      (node (ref "E219") (pin "1") (pinfunction "1_1") (pintype "passive"))
      (node (ref "E237") (pin "1") (pinfunction "1_1") (pintype "passive"))
      (node (ref "E255") (pin "1") (pinfunction "1_1") (pintype "passive"))
      (node (ref "E273") (pin "1") (pinfunction "1_1") (pintype "passive"))
      (node (ref "E291") (pin "1") (pinfunction "1_1") (pintype "passive"))
      (node (ref "E3") (pin "1") (pinfunction "1_1") (pintype "passive"))
      (node (ref "E309") (pin "1") (pinfunction "1_1") (pintype "passive"))
      (node (ref "E39") (pin "1") (pinfunction "1_1") (pintype "passive"))
      (node (ref "E57") (pin "1") (pinfunction "1_1") (pintype "passive"))
      (node (ref "E75") (pin "1") (pinfunction "1_1") (pintype "passive"))
      (node (ref "E93") (pin "1") (pinfunction "1_1") (pintype "passive"))
    )
    (net (code "4") (name "/Col4") (class "Default")
      (node (ref "E112") (pin "1") (pinfunction "1_1") (pintype "passive"))
      (node (ref "E130") (pin "1") (pinfunction "1_1") (pintype "passive"))
      (node (ref "E148") (pin "1") (pinfunction "1_1") (pintype "passive"))
      (node (ref "E166") (pin "1") (pinfunction "1_1") (pintype "passive"))
      (node (ref "E184") (pin "1") (pinfunction "1_1") (pintype "passive"))
      (node (ref "E202") (pin "1") (pinfunction "1_1") (pintype "passive"))
      (node (ref "E22") (pin "1") (pinfunction "1_1") (pintype "passive"))
      (node (ref "E220") (pin "1") (pinfunction "1_1") (pintype "passive"))
      (node (ref "E238") (pin "1") (pinfunction "1_1") (pintype "passive"))
      (node (ref "E256") (pin "1") (pinfunction "1_1") (pintype "passive"))
      (node (ref "E274") (pin "1") (pinfunction "1_1") (pintype "passive"))
      (node (ref "E292") (pin "1") (pinfunction "1_1") (pintype "passive"))
      (node (ref "E310") (pin "1") (pinfunction "1_1") (pintype "passive"))
      (node (ref "E4") (pin "1") (pinfunction "1_1") (pintype "passive"))
      (node (ref "E40") (pin "1") (pinfunction "1_1") (pintype "passive"))
      (node (ref "E58") (pin "1") (pinfunction "1_1") (pintype "passive"))
      (node (ref "E76") (pin "1") (pinfunction "1_1") (pintype "passive"))
      (node (ref "E94") (pin "1") (pinfunction "1_1") (pintype "passive"))
    )
    (net (code "5") (name "/Col5") (class "Default")
      (node (ref "E113") (pin "1") (pinfunction "1_1") (pintype "passive"))
      (node (ref "E131") (pin "1") (pinfunction "1_1") (pintype "passive"))
      (node (ref "E149") (pin "1") (pinfunction "1_1") (pintype "passive"))
      (node (ref "E167") (pin "1") (pinfunction "1_1") (pintype "passive"))
      (node (ref "E185") (pin "1") (pinfunction "1_1") (pintype "passive"))
      (node (ref "E203") (pin "1") (pinfunction "1_1") (pintype "passive"))
      (node (ref "E221") (pin "1") (pinfunction "1_1") (pintype "passive"))
      (node (ref "E23") (pin "1") (pinfunction "1_1") (pintype "passive"))
      (node (ref "E239") (pin "1") (pinfunction "1_1") (pintype "passive"))
      (node (ref "E257") (pin "1") (pinfunction "1_1") (pintype "passive"))
      (node (ref "E275") (pin "1") (pinfunction "1_1") (pintype "passive"))
      (node (ref "E293") (pin "1") (pinfunction "1_1") (pintype "passive"))
      (node (ref "E311") (pin "1") (pinfunction "1_1") (pintype "passive"))
      (node (ref "E41") (pin "1") (pinfunction "1_1") (pintype "passive"))
      (node (ref "E5") (pin "1") (pinfunction "1_1") (pintype "passive"))
      (node (ref "E59") (pin "1") (pinfunction "1_1") (pintype "passive"))
      (node (ref "E77") (pin "1") (pinfunction "1_1") (pintype "passive"))
      (node (ref "E95") (pin "1") (pinfunction "1_1") (pintype "passive"))
    )
    (net (code "6") (name "/Col6") (class "Default")
      (node (ref "E114") (pin "1") (pinfunction "1_1") (pintype "passive"))
      (node (ref "E132") (pin "1") (pinfunction "1_1") (pintype "passive"))
      (node (ref "E150") (pin "1") (pinfunction "1_1") (pintype "passive"))
      (node (ref "E168") (pin "1") (pinfunction "1_1") (pintype "passive"))
      (node (ref "E186") (pin "1") (pinfunction "1_1") (pintype "passive"))
      (node (ref "E204") (pin "1") (pinfunction "1_1") (pintype "passive"))
      (node (ref "E222") (pin "1") (pinfunction "1_1") (pintype "passive"))
      (node (ref "E24") (pin "1") (pinfunction "1_1") (pintype "passive"))
      (node (ref "E240") (pin "1") (pinfunction "1_1") (pintype "passive"))
      (node (ref "E258") (pin "1") (pinfunction "1_1") (pintype "passive"))
      (node (ref "E276") (pin "1") (pinfunction "1_1") (pintype "passive"))
      (node (ref "E294") (pin "1") (pinfunction "1_1") (pintype "passive"))
      (node (ref "E312") (pin "1") (pinfunction "1_1") (pintype "passive"))
      (node (ref "E42") (pin "1") (pinfunction "1_1") (pintype "passive"))
      (node (ref "E6") (pin "1") (pinfunction "1_1") (pintype "passive"))
      (node (ref "E60") (pin "1") (pinfunction "1_1") (pintype "passive"))
      (node (ref "E78") (pin "1") (pinfunction "1_1") (pintype "passive"))
      (node (ref "E96") (pin "1") (pinfunction "1_1") (pintype "passive"))
    )
    (net (code "7") (name "/Col7") (class "Default")
      (node (ref "E115") (pin "1") (pinfunction "1_1") (pintype "passive"))
      (node (ref "E133") (pin "1") (pinfunction "1_1") (pintype "passive"))
      (node (ref "E151") (pin "1") (pinfunction "1_1") (pintype "passive"))
      (node (ref "E169") (pin "1") (pinfunction "1_1") (pintype "passive"))
      (node (ref "E187") (pin "1") (pinfunction "1_1") (pintype "passive"))
      (node (ref "E205") (pin "1") (pinfunction "1_1") (pintype "passive"))
      (node (ref "E223") (pin "1") (pinfunction "1_1") (pintype "passive"))
      (node (ref "E241") (pin "1") (pinfunction "1_1") (pintype "passive"))
      (node (ref "E259") (pin "1") (pinfunction "1_1") (pintype "passive"))
      (node (ref "E277") (pin "1") (pinfunction "1_1") (pintype "passive"))
      (node (ref "E295") (pin "1") (pinfunction "1_1") (pintype "passive"))
      (node (ref "E313") (pin "1") (pinfunction "1_1") (pintype "passive"))
      (node (ref "E43") (pin "1") (pinfunction "1_1") (pintype "passive"))
      (node (ref "E61") (pin "1") (pinfunction "1_1") (pintype "passive"))
      (node (ref "E79") (pin "1") (pinfunction "1_1") (pintype "passive"))
      (node (ref "E97") (pin "1") (pinfunction "1_1") (pintype "passive"))
    )
    (net (code "8") (name "/Col8") (class "Default")
      (node (ref "E116") (pin "1") (pinfunction "1_1") (pintype "passive"))
      (node (ref "E134") (pin "1") (pinfunction "1_1") (pintype "passive"))
      (node (ref "E152") (pin "1") (pinfunction "1_1") (pintype "passive"))
      (node (ref "E170") (pin "1") (pinfunction "1_1") (pintype "passive"))
      (node (ref "E188") (pin "1") (pinfunction "1_1") (pintype "passive"))
      (node (ref "E206") (pin "1") (pinfunction "1_1") (pintype "passive"))
      (node (ref "E224") (pin "1") (pinfunction "1_1") (pintype "passive"))
      (node (ref "E242") (pin "1") (pinfunction "1_1") (pintype "passive"))
      (node (ref "E260") (pin "1") (pinfunction "1_1") (pintype "passive"))
      (node (ref "E278") (pin "1") (pinfunction "1_1") (pintype "passive"))
      (node (ref "E296") (pin "1") (pinfunction "1_1") (pintype "passive"))
      (node (ref "E314") (pin "1") (pinfunction "1_1") (pintype "passive"))
      (node (ref "E62") (pin "1") (pinfunction "1_1") (pintype "passive"))
      (node (ref "E80") (pin "1") (pinfunction "1_1") (pintype "passive"))
      (node (ref "E98") (pin "1") (pinfunction "1_1") (pintype "passive"))
    )
    (net (code "9") (name "/Col9") (class "Default")
      (node (ref "E117") (pin "1") (pinfunction "1_1") (pintype "passive"))
      (node (ref "E135") (pin "1") (pinfunction "1_1") (pintype "passive"))
      (node (ref "E153") (pin "1") (pinfunction "1_1") (pintype "passive"))
      (node (ref "E171") (pin "1") (pinfunction "1_1") (pintype "passive"))
      (node (ref "E189") (pin "1") (pinfunction "1_1") (pintype "passive"))
      (node (ref "E207") (pin "1") (pinfunction "1_1") (pintype "passive"))
      (node (ref "E225") (pin "1") (pinfunction "1_1") (pintype "passive"))
      (node (ref "E243") (pin "1") (pinfunction "1_1") (pintype "passive"))
      (node (ref "E261") (pin "1") (pinfunction "1_1") (pintype "passive"))
      (node (ref "E279") (pin "1") (pinfunction "1_1") (pintype "passive"))
      (node (ref "E297") (pin "1") (pinfunction "1_1") (pintype "passive"))
      (node (ref "E315") (pin "1") (pinfunction "1_1") (pintype "passive"))
      (node (ref "E81") (pin "1") (pinfunction "1_1") (pintype "passive"))
      (node (ref "E99") (pin "1") (pinfunction "1_1") (pintype "passive"))
    )
    (net (code "10") (name "/Col10") (class "Default")
      (node (ref "E100") (pin "1") (pinfunction "1_1") (pintype "passive"))
      (node (ref "E118") (pin "1") (pinfunction "1_1") (pintype "passive"))
      (node (ref "E136") (pin "1") (pinfunction "1_1") (pintype "passive"))
      (node (ref "E154") (pin "1") (pinfunction "1_1") (pintype "passive"))
      (node (ref "E172") (pin "1") (pinfunction "1_1") (pintype "passive"))
      (node (ref "E190") (pin "1") (pinfunction "1_1") (pintype "passive"))
      (node (ref "E208") (pin "1") (pinfunction "1_1") (pintype "passive"))
      (node (ref "E226") (pin "1") (pinfunction "1_1") (pintype "passive"))
      (node (ref "E244") (pin "1") (pinfunction "1_1") (pintype "passive"))
      (node (ref "E262") (pin "1") (pinfunction "1_1") (pintype "passive"))
      (node (ref "E280") (pin "1") (pinfunction "1_1") (pintype "passive"))
      (node (ref "E298") (pin "1") (pinfunction "1_1") (pintype "passive"))
      (node (ref "E316") (pin "1") (pinfunction "1_1") (pintype "passive"))
    )
    (net (code "11") (name "/Col11") (class "Default")
      (node (ref "E101") (pin "1") (pinfunction "1_1") (pintype "passive"))
      (node (ref "E119") (pin "1") (pinfunction "1_1") (pintype "passive"))
      (node (ref "E137") (pin "1") (pinfunction "1_1") (pintype "passive"))
      (node (ref "E155") (pin "1") (pinfunction "1_1") (pintype "passive"))
      (node (ref "E173") (pin "1") (pinfunction "1_1") (pintype "passive"))
      (node (ref "E191") (pin "1") (pinfunction "1_1") (pintype "passive"))
      (node (ref "E209") (pin "1") (pinfunction "1_1") (pintype "passive"))
      (node (ref "E227") (pin "1") (pinfunction "1_1") (pintype "passive"))
      (node (ref "E245") (pin "1") (pinfunction "1_1") (pintype "passive"))
      (node (ref "E263") (pin "1") (pinfunction "1_1") (pintype "passive"))
      (node (ref "E281") (pin "1") (pinfunction "1_1") (pintype "passive"))
      (node (ref "E299") (pin "1") (pinfunction "1_1") (pintype "passive"))
      (node (ref "E317") (pin "1") (pinfunction "1_1") (pintype "passive"))
    )
    (net (code "12") (name "/Col12") (class "Default")
      (node (ref "E102") (pin "1") (pinfunction "1_1") (pintype "passive"))
      (node (ref "E120") (pin "1") (pinfunction "1_1") (pintype "passive"))
      (node (ref "E138") (pin "1") (pinfunction "1_1") (pintype "passive"))
      (node (ref "E156") (pin "1") (pinfunction "1_1") (pintype "passive"))
      (node (ref "E174") (pin "1") (pinfunction "1_1") (pintype "passive"))
      (node (ref "E192") (pin "1") (pinfunction "1_1") (pintype "passive"))
      (node (ref "E210") (pin "1") (pinfunction "1_1") (pintype "passive"))
      (node (ref "E228") (pin "1") (pinfunction "1_1") (pintype "passive"))
      (node (ref "E246") (pin "1") (pinfunction "1_1") (pintype "passive"))
      (node (ref "E264") (pin "1") (pinfunction "1_1") (pintype "passive"))
      (node (ref "E282") (pin "1") (pinfunction "1_1") (pintype "passive"))
      (node (ref "E300") (pin "1") (pinfunction "1_1") (pintype "passive"))
      (node (ref "E318") (pin "1") (pinfunction "1_1") (pintype "passive"))
    )
    (net (code "13") (name "/Col13") (class "Default")
      (node (ref "E103") (pin "1") (pinfunction "1_1") (pintype "passive"))
      (node (ref "E121") (pin "1") (pinfunction "1_1") (pintype "passive"))
      (node (ref "E139") (pin "1") (pinfunction "1_1") (pintype "passive"))
      (node (ref "E157") (pin "1") (pinfunction "1_1") (pintype "passive"))
      (node (ref "E175") (pin "1") (pinfunction "1_1") (pintype "passive"))
      (node (ref "E193") (pin "1") (pinfunction "1_1") (pintype "passive"))
      (node (ref "E211") (pin "1") (pinfunction "1_1") (pintype "passive"))
      (node (ref "E229") (pin "1") (pinfunction "1_1") (pintype "passive"))
      (node (ref "E247") (pin "1") (pinfunction "1_1") (pintype "passive"))
      (node (ref "E265") (pin "1") (pinfunction "1_1") (pintype "passive"))
      (node (ref "E283") (pin "1") (pinfunction "1_1") (pintype "passive"))
      (node (ref "E301") (pin "1") (pinfunction "1_1") (pintype "passive"))
      (node (ref "E319") (pin "1") (pinfunction "1_1") (pintype "passive"))
    )
    (net (code "14") (name "/Col14") (class "Default")
      (node (ref "E104") (pin "1") (pinfunction "1_1") (pintype "passive"))
      (node (ref "E122") (pin "1") (pinfunction "1_1") (pintype "passive"))
      (node (ref "E140") (pin "1") (pinfunction "1_1") (pintype "passive"))
      (node (ref "E158") (pin "1") (pinfunction "1_1") (pintype "passive"))
      (node (ref "E176") (pin "1") (pinfunction "1_1") (pintype "passive"))
      (node (ref "E194") (pin "1") (pinfunction "1_1") (pintype "passive"))
      (node (ref "E212") (pin "1") (pinfunction "1_1") (pintype "passive"))
      (node (ref "E230") (pin "1") (pinfunction "1_1") (pintype "passive"))
      (node (ref "E248") (pin "1") (pinfunction "1_1") (pintype "passive"))
      (node (ref "E266") (pin "1") (pinfunction "1_1") (pintype "passive"))
      (node (ref "E284") (pin "1") (pinfunction "1_1") (pintype "passive"))
      (node (ref "E302") (pin "1") (pinfunction "1_1") (pintype "passive"))
      (node (ref "E320") (pin "1") (pinfunction "1_1") (pintype "passive"))
    )
    (net (code "15") (name "/Col15") (class "Default")
      (node (ref "E105") (pin "1") (pinfunction "1_1") (pintype "passive"))
      (node (ref "E123") (pin "1") (pinfunction "1_1") (pintype "passive"))
      (node (ref "E141") (pin "1") (pinfunction "1_1") (pintype "passive"))
      (node (ref "E159") (pin "1") (pinfunction "1_1") (pintype "passive"))
      (node (ref "E177") (pin "1") (pinfunction "1_1") (pintype "passive"))
      (node (ref "E195") (pin "1") (pinfunction "1_1") (pintype "passive"))
      (node (ref "E213") (pin "1") (pinfunction "1_1") (pintype "passive"))
      (node (ref "E231") (pin "1") (pinfunction "1_1") (pintype "passive"))
      (node (ref "E249") (pin "1") (pinfunction "1_1") (pintype "passive"))
      (node (ref "E267") (pin "1") (pinfunction "1_1") (pintype "passive"))
      (node (ref "E285") (pin "1") (pinfunction "1_1") (pintype "passive"))
      (node (ref "E303") (pin "1") (pinfunction "1_1") (pintype "passive"))
      (node (ref "E321") (pin "1") (pinfunction "1_1") (pintype "passive"))
    )
    (net (code "16") (name "/Col16") (class "Default")
      (node (ref "E106") (pin "1") (pinfunction "1_1") (pintype "passive"))
      (node (ref "E124") (pin "1") (pinfunction "1_1") (pintype "passive"))
      (node (ref "E142") (pin "1") (pinfunction "1_1") (pintype "passive"))
      (node (ref "E160") (pin "1") (pinfunction "1_1") (pintype "passive"))
      (node (ref "E178") (pin "1") (pinfunction "1_1") (pintype "passive"))
      (node (ref "E196") (pin "1") (pinfunction "1_1") (pintype "passive"))
      (node (ref "E214") (pin "1") (pinfunction "1_1") (pintype "passive"))
      (node (ref "E232") (pin "1") (pinfunction "1_1") (pintype "passive"))
      (node (ref "E250") (pin "1") (pinfunction "1_1") (pintype "passive"))
      (node (ref "E268") (pin "1") (pinfunction "1_1") (pintype "passive"))
      (node (ref "E286") (pin "1") (pinfunction "1_1") (pintype "passive"))
      (node (ref "E304") (pin "1") (pinfunction "1_1") (pintype "passive"))
      (node (ref "E322") (pin "1") (pinfunction "1_1") (pintype "passive"))
    )
    (net (code "17") (name "/Col17") (class "Default")
      (node (ref "E107") (pin "1") (pinfunction "1_1") (pintype "passive"))
      (node (ref "E125") (pin "1") (pinfunction "1_1") (pintype "passive"))
      (node (ref "E143") (pin "1") (pinfunction "1_1") (pintype "passive"))
      (node (ref "E161") (pin "1") (pinfunction "1_1") (pintype "passive"))
      (node (ref "E179") (pin "1") (pinfunction "1_1") (pintype "passive"))
      (node (ref "E197") (pin "1") (pinfunction "1_1") (pintype "passive"))
      (node (ref "E215") (pin "1") (pinfunction "1_1") (pintype "passive"))
      (node (ref "E233") (pin "1") (pinfunction "1_1") (pintype "passive"))
      (node (ref "E251") (pin "1") (pinfunction "1_1") (pintype "passive"))
      (node (ref "E269") (pin "1") (pinfunction "1_1") (pintype "passive"))
      (node (ref "E287") (pin "1") (pinfunction "1_1") (pintype "passive"))
      (node (ref "E305") (pin "1") (pinfunction "1_1") (pintype "passive"))
      (node (ref "E323") (pin "1") (pinfunction "1_1") (pintype "passive"))
    )
    (net (code "18") (name "/Col18") (class "Default")
      (node (ref "E108") (pin "1") (pinfunction "1_1") (pintype "passive"))
      (node (ref "E126") (pin "1") (pinfunction "1_1") (pintype "passive"))
      (node (ref "E144") (pin "1") (pinfunction "1_1") (pintype "passive"))
      (node (ref "E162") (pin "1") (pinfunction "1_1") (pintype "passive"))
      (node (ref "E180") (pin "1") (pinfunction "1_1") (pintype "passive"))
      (node (ref "E198") (pin "1") (pinfunction "1_1") (pintype "passive"))
      (node (ref "E216") (pin "1") (pinfunction "1_1") (pintype "passive"))
      (node (ref "E234") (pin "1") (pinfunction "1_1") (pintype "passive"))
      (node (ref "E252") (pin "1") (pinfunction "1_1") (pintype "passive"))
      (node (ref "E270") (pin "1") (pinfunction "1_1") (pintype "passive"))
      (node (ref "E288") (pin "1") (pinfunction "1_1") (pintype "passive"))
      (node (ref "E306") (pin "1") (pinfunction "1_1") (pintype "passive"))
      (node (ref "E324") (pin "1") (pinfunction "1_1") (pintype "passive"))
    )
    (net (code "19") (name "/Row1") (class "Default")
      (node (ref "E1") (pin "0") (pinfunction "0_0") (pintype "passive"))
      (node (ref "E2") (pin "0") (pinfunction "0_0") (pintype "passive"))
      (node (ref "E3") (pin "0") (pinfunction "0_0") (pintype "passive"))
      (node (ref "E4") (pin "0") (pinfunction "0_0") (pintype "passive"))
      (node (ref "E5") (pin "0") (pinfunction "0_0") (pintype "passive"))
      (node (ref "E6") (pin "0") (pinfunction "0_0") (pintype "passive"))
    )
    (net (code "20") (name "/Row2") (class "Default")
      (node (ref "E19") (pin "0") (pinfunction "0_0") (pintype "passive"))
      (node (ref "E20") (pin "0") (pinfunction "0_0") (pintype "passive"))
      (node (ref "E21") (pin "0") (pinfunction "0_0") (pintype "passive"))
      (node (ref "E22") (pin "0") (pinfunction "0_0") (pintype "passive"))
      (node (ref "E23") (pin "0") (pinfunction "0_0") (pintype "passive"))
      (node (ref "E24") (pin "0") (pinfunction "0_0") (pintype "passive"))
    )
    (net (code "21") (name "/Row3") (class "Default")
      (node (ref "E37") (pin "0") (pinfunction "0_0") (pintype "passive"))
      (node (ref "E38") (pin "0") (pinfunction "0_0") (pintype "passive"))
      (node (ref "E39") (pin "0") (pinfunction "0_0") (pintype "passive"))
      (node (ref "E40") (pin "0") (pinfunction "0_0") (pintype "passive"))
      (node (ref "E41") (pin "0") (pinfunction "0_0") (pintype "passive"))
      (node (ref "E42") (pin "0") (pinfunction "0_0") (pintype "passive"))
      (node (ref "E43") (pin "0") (pinfunction "0_0") (pintype "passive"))
    )
    (net (code "22") (name "/Row4") (class "Default")
      (node (ref "E55") (pin "0") (pinfunction "0_0") (pintype "passive"))
      (node (ref "E56") (pin "0") (pinfunction "0_0") (pintype "passive"))
      (node (ref "E57") (pin "0") (pinfunction "0_0") (pintype "passive"))
      (node (ref "E58") (pin "0") (pinfunction "0_0") (pintype "passive"))
      (node (ref "E59") (pin "0") (pinfunction "0_0") (pintype "passive"))
      (node (ref "E60") (pin "0") (pinfunction "0_0") (pintype "passive"))
      (node (ref "E61") (pin "0") (pinfunction "0_0") (pintype "passive"))
      (node (ref "E62") (pin "0") (pinfunction "0_0") (pintype "passive"))
    )
    (net (code "23") (name "/Row5") (class "Default")
      (node (ref "E73") (pin "0") (pinfunction "0_0") (pintype "passive"))
      (node (ref "E74") (pin "0") (pinfunction "0_0") (pintype "passive"))
      (node (ref "E75") (pin "0") (pinfunction "0_0") (pintype "passive"))
      (node (ref "E76") (pin "0") (pinfunction "0_0") (pintype "passive"))
      (node (ref "E77") (pin "0") (pinfunction "0_0") (pintype "passive"))
      (node (ref "E78") (pin "0") (pinfunction "0_0") (pintype "passive"))
      (node (ref "E79") (pin "0") (pinfunction "0_0") (pintype "passive"))
      (node (ref "E80") (pin "0") (pinfunction "0_0") (pintype "passive"))
      (node (ref "E81") (pin "0") (pinfunction "0_0") (pintype "passive"))
    )
    (net (code "24") (name "/Row6") (class "Default")
      (node (ref "E100") (pin "0") (pinfunction "0_0") (pintype "passive"))
      (node (ref "E101") (pin "0") (pinfunction "0_0") (pintype "passive"))
      (node (ref "E102") (pin "0") (pinfunction "0_0") (pintype "passive"))
      (node (ref "E103") (pin "0") (pinfunction "0_0") (pintype "passive"))
      (node (ref "E104") (pin "0") (pinfunction "0_0") (pintype "passive"))
      (node (ref "E105") (pin "0") (pinfunction "0_0") (pintype "passive"))
      (node (ref "E106") (pin "0") (pinfunction "0_0") (pintype "passive"))
      (node (ref "E107") (pin "0") (pinfunction "0_0") (pintype "passive"))
      (node (ref "E108") (pin "0") (pinfunction "0_0") (pintype "passive"))
      (node (ref "E91") (pin "0") (pinfunction "0_0") (pintype "passive"))
      (node (ref "E92") (pin "0") (pinfunction "0_0") (pintype "passive"))
      (node (ref "E93") (pin "0") (pinfunction "0_0") (pintype "passive"))
      (node (ref "E94") (pin "0") (pinfunction "0_0") (pintype "passive"))
      (node (ref "E95") (pin "0") (pinfunction "0_0") (pintype "passive"))
      (node (ref "E96") (pin "0") (pinfunction "0_0") (pintype "passive"))
      (node (ref "E97") (pin "0") (pinfunction "0_0") (pintype "passive"))
      (node (ref "E98") (pin "0") (pinfunction "0_0") (pintype "passive"))
      (node (ref "E99") (pin "0") (pinfunction "0_0") (pintype "passive"))
    )
    (net (code "25") (name "/Row7") (class "Default")
      (node (ref "E109") (pin "0") (pinfunction "0_0") (pintype "passive"))
      (node (ref "E110") (pin "0") (pinfunction "0_0") (pintype "passive"))
      (node (ref "E111") (pin "0") (pinfunction "0_0") (pintype "passive"))
      (node (ref "E112") (pin "0") (pinfunction "0_0") (pintype "passive"))
      (node (ref "E113") (pin "0") (pinfunction "0_0") (pintype "passive"))
      (node (ref "E114") (pin "0") (pinfunction "0_0") (pintype "passive"))
      (node (ref "E115") (pin "0") (pinfunction "0_0") (pintype "passive"))
      (node (ref "E116") (pin "0") (pinfunction "0_0") (pintype "passive"))
      (node (ref "E117") (pin "0") (pinfunction "0_0") (pintype "passive"))
      (node (ref "E118") (pin "0") (pinfunction "0_0") (pintype "passive"))
      (node (ref "E119") (pin "0") (pinfunction "0_0") (pintype "passive"))
      (node (ref "E120") (pin "0") (pinfunction "0_0") (pintype "passive"))
      (node (ref "E121") (pin "0") (pinfunction "0_0") (pintype "passive"))
      (node (ref "E122") (pin "0") (pinfunction "0_0") (pintype "passive"))
      (node (ref "E123") (pin "0") (pinfunction "0_0") (pintype "passive"))
      (node (ref "E124") (pin "0") (pinfunction "0_0") (pintype "passive"))
      (node (ref "E125") (pin "0") (pinfunction "0_0") (pintype "passive"))
      (node (ref "E126") (pin "0") (pinfunction "0_0") (pintype "passive"))
    )
    (net (code "26") (name "/Row8") (class "Default")
      (node (ref "E127") (pin "0") (pinfunction "0_0") (pintype "passive"))
      (node (ref "E128") (pin "0") (pinfunction "0_0") (pintype "passive"))
      (node (ref "E129") (pin "0") (pinfunction "0_0") (pintype "passive"))
      (node (ref "E130") (pin "0") (pinfunction "0_0") (pintype "passive"))
      (node (ref "E131") (pin "0") (pinfunction "0_0") (pintype "passive"))
      (node (ref "E132") (pin "0") (pinfunction "0_0") (pintype "passive"))
      (node (ref "E133") (pin "0") (pinfunction "0_0") (pintype "passive"))
      (node (ref "E134") (pin "0") (pinfunction "0_0") (pintype "passive"))
      (node (ref "E135") (pin "0") (pinfunction "0_0") (pintype "passive"))
      (node (ref "E136") (pin "0") (pinfunction "0_0") (pintype "passive"))
      (node (ref "E137") (pin "0") (pinfunction "0_0") (pintype "passive"))
      (node (ref "E138") (pin "0") (pinfunction "0_0") (pintype "passive"))
      (node (ref "E139") (pin "0") (pinfunction "0_0") (pintype "passive"))
      (node (ref "E140") (pin "0") (pinfunction "0_0") (pintype "passive"))
      (node (ref "E141") (pin "0") (pinfunction "0_0") (pintype "passive"))
      (node (ref "E142") (pin "0") (pinfunction "0_0") (pintype "passive"))
      (node (ref "E143") (pin "0") (pinfunction "0_0") (pintype "passive"))
      (node (ref "E144") (pin "0") (pinfunction "0_0") (pintype "passive"))
    )
    (net (code "27") (name "/Row9") (class "Default")
      (node (ref "E145") (pin "0") (pinfunction "0_0") (pintype "passive"))
      (node (ref "E146") (pin "0") (pinfunction "0_0") (pintype "passive"))
      (node (ref "E147") (pin "0") (pinfunction "0_0") (pintype "passive"))
      (node (ref "E148") (pin "0") (pinfunction "0_0") (pintype "passive"))
      (node (ref "E149") (pin "0") (pinfunction "0_0") (pintype "passive"))
      (node (ref "E150") (pin "0") (pinfunction "0_0") (pintype "passive"))
      (node (ref "E151") (pin "0") (pinfunction "0_0") (pintype "passive"))
      (node (ref "E152") (pin "0") (pinfunction "0_0") (pintype "passive"))
      (node (ref "E153") (pin "0") (pinfunction "0_0") (pintype "passive"))
      (node (ref "E154") (pin "0") (pinfunction "0_0") (pintype "passive"))
      (node (ref "E155") (pin "0") (pinfunction "0_0") (pintype "passive"))
      (node (ref "E156") (pin "0") (pinfunction "0_0") (pintype "passive"))
      (node (ref "E157") (pin "0") (pinfunction "0_0") (pintype "passive"))
      (node (ref "E158") (pin "0") (pinfunction "0_0") (pintype "passive"))
      (node (ref "E159") (pin "0") (pinfunction "0_0") (pintype "passive"))
      (node (ref "E160") (pin "0") (pinfunction "0_0") (pintype "passive"))
      (node (ref "E161") (pin "0") (pinfunction "0_0") (pintype "passive"))
      (node (ref "E162") (pin "0") (pinfunction "0_0") (pintype "passive"))
    )
    (net (code "28") (name "/Row10") (class "Default")
      (node (ref "E163") (pin "0") (pinfunction "0_0") (pintype "passive"))
      (node (ref "E164") (pin "0") (pinfunction "0_0") (pintype "passive"))
      (node (ref "E165") (pin "0") (pinfunction "0_0") (pintype "passive"))
      (node (ref "E166") (pin "0") (pinfunction "0_0") (pintype "passive"))
      (node (ref "E167") (pin "0") (pinfunction "0_0") (pintype "passive"))
      (node (ref "E168") (pin "0") (pinfunction "0_0") (pintype "passive"))
      (node (ref "E169") (pin "0") (pinfunction "0_0") (pintype "passive"))
      (node (ref "E170") (pin "0") (pinfunction "0_0") (pintype "passive"))
      (node (ref "E171") (pin "0") (pinfunction "0_0") (pintype "passive"))
      (node (ref "E172") (pin "0") (pinfunction "0_0") (pintype "passive"))
      (node (ref "E173") (pin "0") (pinfunction "0_0") (pintype "passive"))
      (node (ref "E174") (pin "0") (pinfunction "0_0") (pintype "passive"))
      (node (ref "E175") (pin "0") (pinfunction "0_0") (pintype "passive"))
      (node (ref "E176") (pin "0") (pinfunction "0_0") (pintype "passive"))
      (node (ref "E177") (pin "0") (pinfunction "0_0") (pintype "passive"))
      (node (ref "E178") (pin "0") (pinfunction "0_0") (pintype "passive"))
      (node (ref "E179") (pin "0") (pinfunction "0_0") (pintype "passive"))
      (node (ref "E180") (pin "0") (pinfunction "0_0") (pintype "passive"))
    )
    (net (code "29") (name "/Row11") (class "Default")
      (node (ref "E181") (pin "0") (pinfunction "0_0") (pintype "passive"))
      (node (ref "E182") (pin "0") (pinfunction "0_0") (pintype "passive"))
      (node (ref "E183") (pin "0") (pinfunction "0_0") (pintype "passive"))
      (node (ref "E184") (pin "0") (pinfunction "0_0") (pintype "passive"))
      (node (ref "E185") (pin "0") (pinfunction "0_0") (pintype "passive"))
      (node (ref "E186") (pin "0") (pinfunction "0_0") (pintype "passive"))
      (node (ref "E187") (pin "0") (pinfunction "0_0") (pintype "passive"))
      (node (ref "E188") (pin "0") (pinfunction "0_0") (pintype "passive"))
      (node (ref "E189") (pin "0") (pinfunction "0_0") (pintype "passive"))
      (node (ref "E190") (pin "0") (pinfunction "0_0") (pintype "passive"))
      (node (ref "E191") (pin "0") (pinfunction "0_0") (pintype "passive"))
      (node (ref "E192") (pin "0") (pinfunction "0_0") (pintype "passive"))
      (node (ref "E193") (pin "0") (pinfunction "0_0") (pintype "passive"))
      (node (ref "E194") (pin "0") (pinfunction "0_0") (pintype "passive"))
      (node (ref "E195") (pin "0") (pinfunction "0_0") (pintype "passive"))
      (node (ref "E196") (pin "0") (pinfunction "0_0") (pintype "passive"))
      (node (ref "E197") (pin "0") (pinfunction "0_0") (pintype "passive"))
      (node (ref "E198") (pin "0") (pinfunction "0_0") (pintype "passive"))
    )
    (net (code "30") (name "/Row12") (class "Default")
      (node (ref "E199") (pin "0") (pinfunction "0_0") (pintype "passive"))
      (node (ref "E200") (pin "0") (pinfunction "0_0") (pintype "passive"))
      (node (ref "E201") (pin "0") (pinfunction "0_0") (pintype "passive"))
      (node (ref "E202") (pin "0") (pinfunction "0_0") (pintype "passive"))
      (node (ref "E203") (pin "0") (pinfunction "0_0") (pintype "passive"))
      (node (ref "E204") (pin "0") (pinfunction "0_0") (pintype "passive"))
      (node (ref "E205") (pin "0") (pinfunction "0_0") (pintype "passive"))
      (node (ref "E206") (pin "0") (pinfunction "0_0") (pintype "passive"))
      (node (ref "E207") (pin "0") (pinfunction "0_0") (pintype "passive"))
      (node (ref "E208") (pin "0") (pinfunction "0_0") (pintype "passive"))
      (node (ref "E209") (pin "0") (pinfunction "0_0") (pintype "passive"))
      (node (ref "E210") (pin "0") (pinfunction "0_0") (pintype "passive"))
      (node (ref "E211") (pin "0") (pinfunction "0_0") (pintype "passive"))
      (node (ref "E212") (pin "0") (pinfunction "0_0") (pintype "passive"))
      (node (ref "E213") (pin "0") (pinfunction "0_0") (pintype "passive"))
      (node (ref "E214") (pin "0") (pinfunction "0_0") (pintype "passive"))
      (node (ref "E215") (pin "0") (pinfunction "0_0") (pintype "passive"))
      (node (ref "E216") (pin "0") (pinfunction "0_0") (pintype "passive"))
    )
    (net (code "31") (name "/Row13") (class "Default")
      (node (ref "E217") (pin "0") (pinfunction "0_0") (pintype "passive"))
      (node (ref "E218") (pin "0") (pinfunction "0_0") (pintype "passive"))
      (node (ref "E219") (pin "0") (pinfunction "0_0") (pintype "passive"))
      (node (ref "E220") (pin "0") (pinfunction "0_0") (pintype "passive"))
      (node (ref "E221") (pin "0") (pinfunction "0_0") (pintype "passive"))
      (node (ref "E222") (pin "0") (pinfunction "0_0") (pintype "passive"))
      (node (ref "E223") (pin "0") (pinfunction "0_0") (pintype "passive"))
      (node (ref "E224") (pin "0") (pinfunction "0_0") (pintype "passive"))
      (node (ref "E225") (pin "0") (pinfunction "0_0") (pintype "passive"))
      (node (ref "E226") (pin "0") (pinfunction "0_0") (pintype "passive"))
      (node (ref "E227") (pin "0") (pinfunction "0_0") (pintype "passive"))
      (node (ref "E228") (pin "0") (pinfunction "0_0") (pintype "passive"))
      (node (ref "E229") (pin "0") (pinfunction "0_0") (pintype "passive"))
      (node (ref "E230") (pin "0") (pinfunction "0_0") (pintype "passive"))
      (node (ref "E231") (pin "0") (pinfunction "0_0") (pintype "passive"))
      (node (ref "E232") (pin "0") (pinfunction "0_0") (pintype "passive"))
      (node (ref "E233") (pin "0") (pinfunction "0_0") (pintype "passive"))
      (node (ref "E234") (pin "0") (pinfunction "0_0") (pintype "passive"))
    )
    (net (code "32") (name "/Row14") (class "Default")
      (node (ref "E235") (pin "0") (pinfunction "0_0") (pintype "passive"))
      (node (ref "E236") (pin "0") (pinfunction "0_0") (pintype "passive"))
      (node (ref "E237") (pin "0") (pinfunction "0_0") (pintype "passive"))
      (node (ref "E238") (pin "0") (pinfunction "0_0") (pintype "passive"))
      (node (ref "E239") (pin "0") (pinfunction "0_0") (pintype "passive"))
      (node (ref "E240") (pin "0") (pinfunction "0_0") (pintype "passive"))
      (node (ref "E241") (pin "0") (pinfunction "0_0") (pintype "passive"))
      (node (ref "E242") (pin "0") (pinfunction "0_0") (pintype "passive"))
      (node (ref "E243") (pin "0") (pinfunction "0_0") (pintype "passive"))
      (node (ref "E244") (pin "0") (pinfunction "0_0") (pintype "passive"))
      (node (ref "E245") (pin "0") (pinfunction "0_0") (pintype "passive"))
      (node (ref "E246") (pin "0") (pinfunction "0_0") (pintype "passive"))
      (node (ref "E247") (pin "0") (pinfunction "0_0") (pintype "passive"))
      (node (ref "E248") (pin "0") (pinfunction "0_0") (pintype "passive"))
      (node (ref "E249") (pin "0") (pinfunction "0_0") (pintype "passive"))
      (node (ref "E250") (pin "0") (pinfunction "0_0") (pintype "passive"))
      (node (ref "E251") (pin "0") (pinfunction "0_0") (pintype "passive"))
      (node (ref "E252") (pin "0") (pinfunction "0_0") (pintype "passive"))
    )
    (net (code "33") (name "/Row15") (class "Default")
      (node (ref "E253") (pin "0") (pinfunction "0_0") (pintype "passive"))
      (node (ref "E254") (pin "0") (pinfunction "0_0") (pintype "passive"))
      (node (ref "E255") (pin "0") (pinfunction "0_0") (pintype "passive"))
      (node (ref "E256") (pin "0") (pinfunction "0_0") (pintype "passive"))
      (node (ref "E257") (pin "0") (pinfunction "0_0") (pintype "passive"))
      (node (ref "E258") (pin "0") (pinfunction "0_0") (pintype "passive"))
      (node (ref "E259") (pin "0") (pinfunction "0_0") (pintype "passive"))
      (node (ref "E260") (pin "0") (pinfunction "0_0") (pintype "passive"))
      (node (ref "E261") (pin "0") (pinfunction "0_0") (pintype "passive"))
      (node (ref "E262") (pin "0") (pinfunction "0_0") (pintype "passive"))
      (node (ref "E263") (pin "0") (pinfunction "0_0") (pintype "passive"))
      (node (ref "E264") (pin "0") (pinfunction "0_0") (pintype "passive"))
      (node (ref "E265") (pin "0") (pinfunction "0_0") (pintype "passive"))
      (node (ref "E266") (pin "0") (pinfunction "0_0") (pintype "passive"))
      (node (ref "E267") (pin "0") (pinfunction "0_0") (pintype "passive"))
      (node (ref "E268") (pin "0") (pinfunction "0_0") (pintype "passive"))
      (node (ref "E269") (pin "0") (pinfunction "0_0") (pintype "passive"))
      (node (ref "E270") (pin "0") (pinfunction "0_0") (pintype "passive"))
    )
    (net (code "34") (name "/Row16") (class "Default")
      (node (ref "E271") (pin "0") (pinfunction "0_0") (pintype "passive"))
      (node (ref "E272") (pin "0") (pinfunction "0_0") (pintype "passive"))
      (node (ref "E273") (pin "0") (pinfunction "0_0") (pintype "passive"))
      (node (ref "E274") (pin "0") (pinfunction "0_0") (pintype "passive"))
      (node (ref "E275") (pin "0") (pinfunction "0_0") (pintype "passive"))
      (node (ref "E276") (pin "0") (pinfunction "0_0") (pintype "passive"))
      (node (ref "E277") (pin "0") (pinfunction "0_0") (pintype "passive"))
      (node (ref "E278") (pin "0") (pinfunction "0_0") (pintype "passive"))
      (node (ref "E279") (pin "0") (pinfunction "0_0") (pintype "passive"))
      (node (ref "E280") (pin "0") (pinfunction "0_0") (pintype "passive"))
      (node (ref "E281") (pin "0") (pinfunction "0_0") (pintype "passive"))
      (node (ref "E282") (pin "0") (pinfunction "0_0") (pintype "passive"))
      (node (ref "E283") (pin "0") (pinfunction "0_0") (pintype "passive"))
      (node (ref "E284") (pin "0") (pinfunction "0_0") (pintype "passive"))
      (node (ref "E285") (pin "0") (pinfunction "0_0") (pintype "passive"))
      (node (ref "E286") (pin "0") (pinfunction "0_0") (pintype "passive"))
      (node (ref "E287") (pin "0") (pinfunction "0_0") (pintype "passive"))
      (node (ref "E288") (pin "0") (pinfunction "0_0") (pintype "passive"))
      (node (ref "E289") (pin "0") (pinfunction "0_0") (pintype "passive"))
      (node (ref "E290") (pin "0") (pinfunction "0_0") (pintype "passive"))
      (node (ref "E291") (pin "0") (pinfunction "0_0") (pintype "passive"))
      (node (ref "E292") (pin "0") (pinfunction "0_0") (pintype "passive"))
      (node (ref "E293") (pin "0") (pinfunction "0_0") (pintype "passive"))
      (node (ref "E294") (pin "0") (pinfunction "0_0") (pintype "passive"))
      (node (ref "E295") (pin "0") (pinfunction "0_0") (pintype "passive"))
      (node (ref "E296") (pin "0") (pinfunction "0_0") (pintype "passive"))
      (node (ref "E297") (pin "0") (pinfunction "0_0") (pintype "passive"))
      (node (ref "E298") (pin "0") (pinfunction "0_0") (pintype "passive"))
      (node (ref "E299") (pin "0") (pinfunction "0_0") (pintype "passive"))
      (node (ref "E300") (pin "0") (pinfunction "0_0") (pintype "passive"))
      (node (ref "E301") (pin "0") (pinfunction "0_0") (pintype "passive"))
      (node (ref "E302") (pin "0") (pinfunction "0_0") (pintype "passive"))
      (node (ref "E303") (pin "0") (pinfunction "0_0") (pintype "passive"))
      (node (ref "E304") (pin "0") (pinfunction "0_0") (pintype "passive"))
      (node (ref "E305") (pin "0") (pinfunction "0_0") (pintype "passive"))
      (node (ref "E306") (pin "0") (pinfunction "0_0") (pintype "passive"))
      (node (ref "E307") (pin "0") (pinfunction "0_0") (pintype "passive"))
      (node (ref "E308") (pin "0") (pinfunction "0_0") (pintype "passive"))
      (node (ref "E309") (pin "0") (pinfunction "0_0") (pintype "passive"))
      (node (ref "E310") (pin "0") (pinfunction "0_0") (pintype "passive"))
      (node (ref "E311") (pin "0") (pinfunction "0_0") (pintype "passive"))
      (node (ref "E312") (pin "0") (pinfunction "0_0") (pintype "passive"))
      (node (ref "E313") (pin "0") (pinfunction "0_0") (pintype "passive"))
      (node (ref "E314") (pin "0") (pinfunction "0_0") (pintype "passive"))
      (node (ref "E315") (pin "0") (pinfunction "0_0") (pintype "passive"))
      (node (ref "E316") (pin "0") (pinfunction "0_0") (pintype "passive"))
      (node (ref "E317") (pin "0") (pinfunction "0_0") (pintype "passive"))
      (node (ref "E318") (pin "0") (pinfunction "0_0") (pintype "passive"))
      (node (ref "E319") (pin "0") (pinfunction "0_0") (pintype "passive"))
      (node (ref "E320") (pin "0") (pinfunction "0_0") (pintype "passive"))
      (node (ref "E321") (pin "0") (pinfunction "0_0") (pintype "passive"))
      (node (ref "E322") (pin "0") (pinfunction "0_0") (pintype "passive"))
      (node (ref "E323") (pin "0") (pinfunction "0_0") (pintype "passive"))
      (node (ref "E324") (pin "0") (pinfunction "0_0") (pintype "passive"))
    )
  )
)
